# couch-int-rc.net
KiCad netlist of a schematic drawn in EAGLE
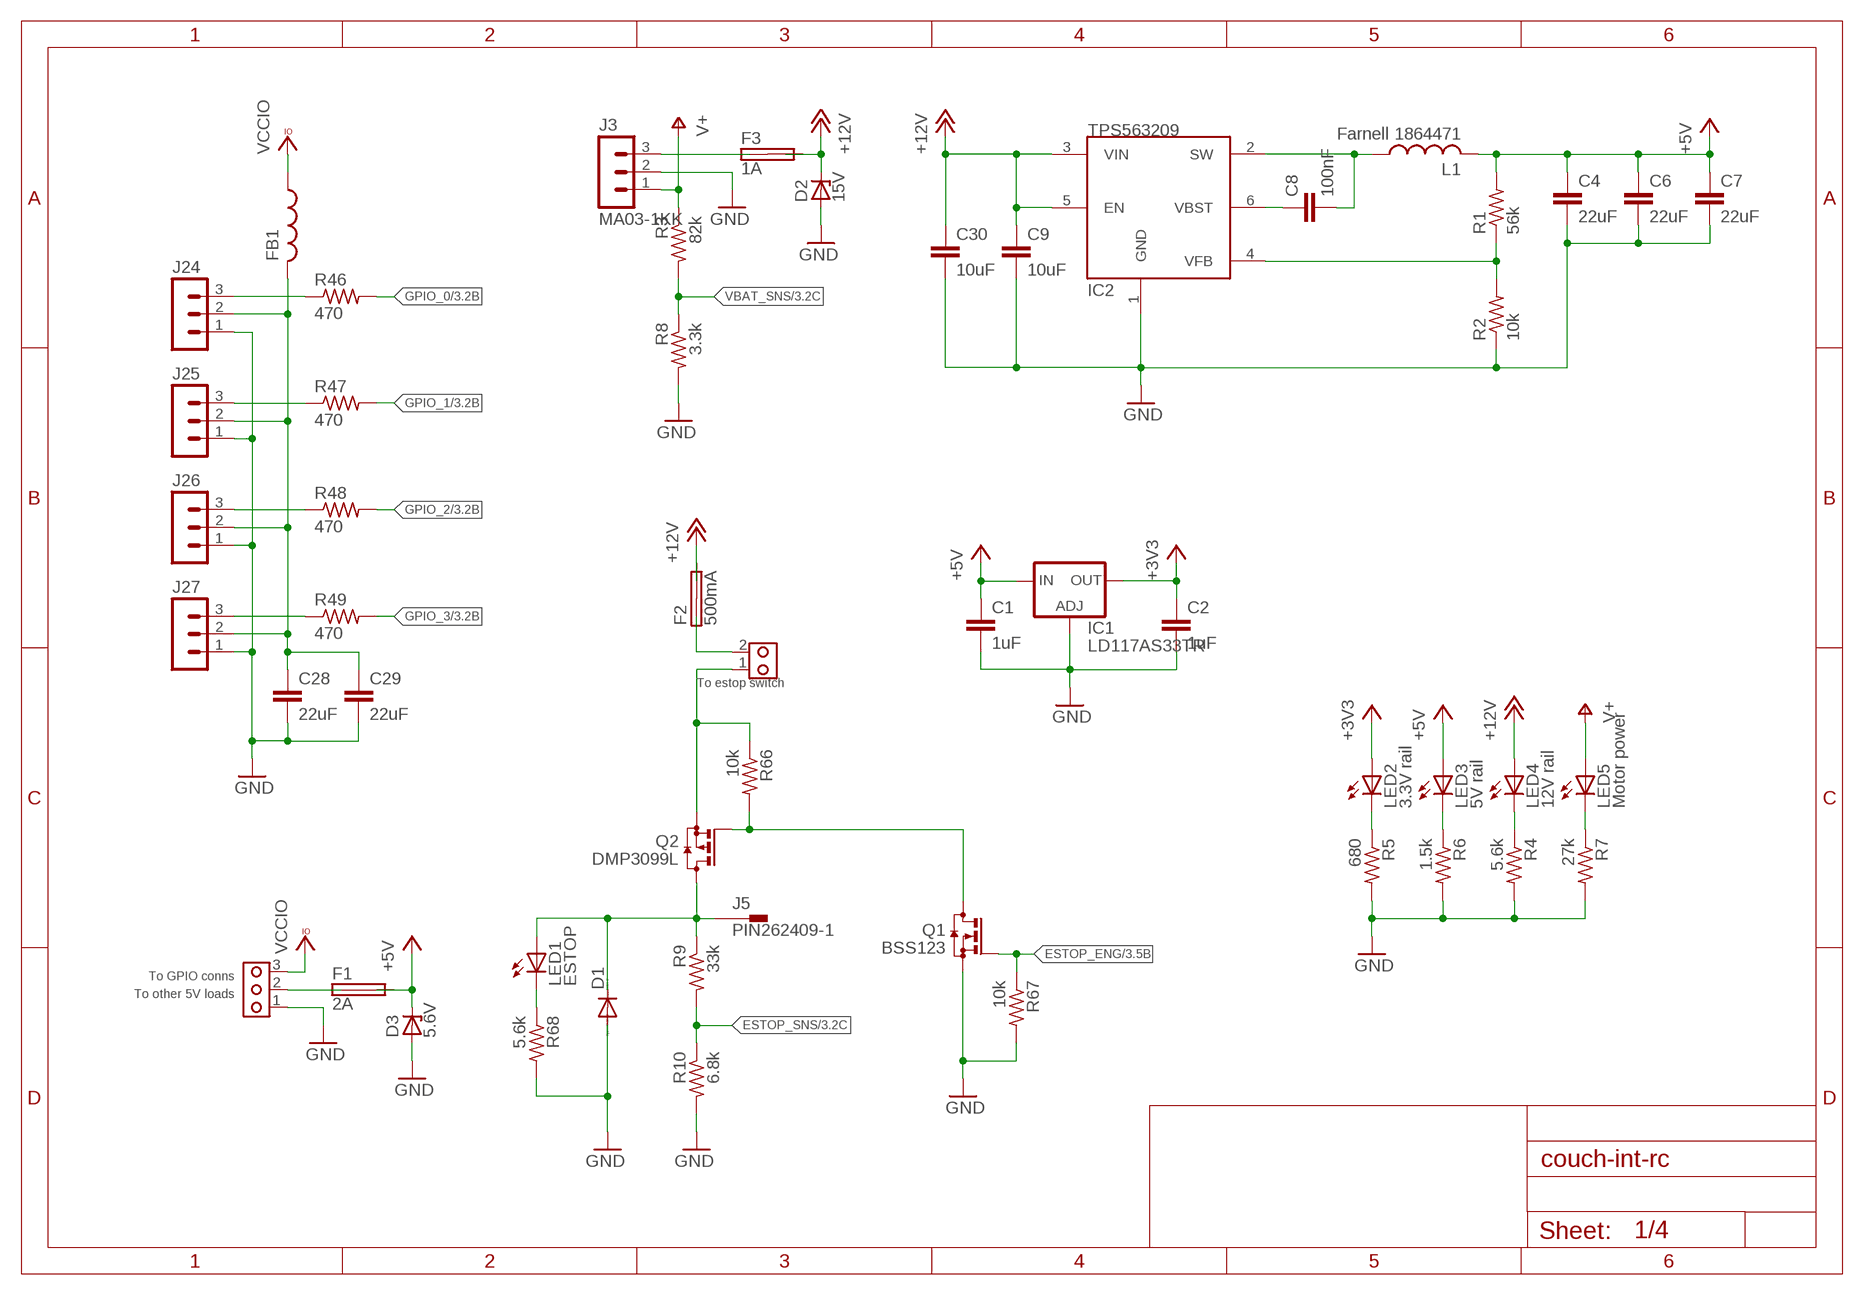
[diagram p0: schematic, sheet 1]
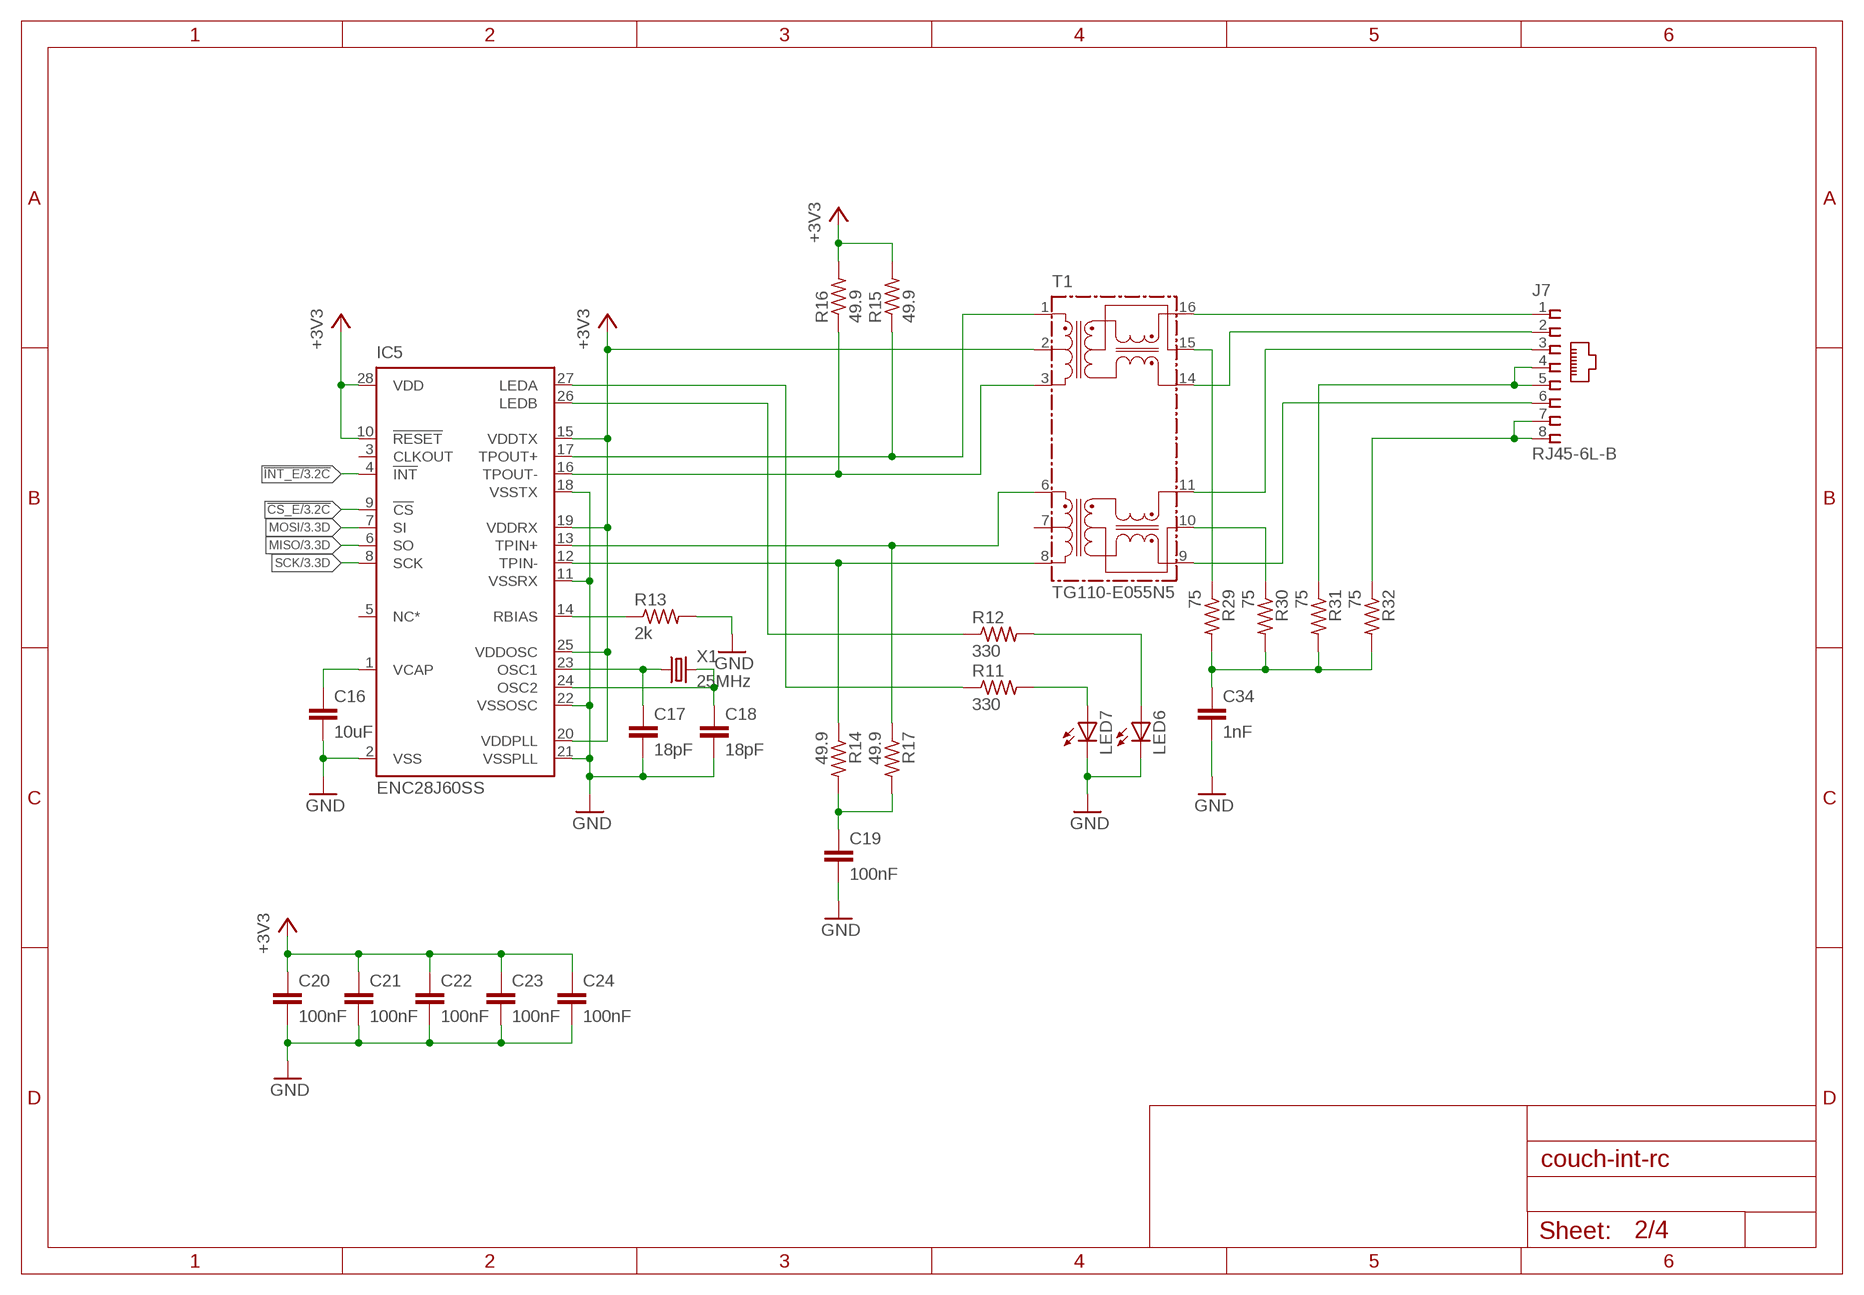
[diagram p1: schematic, sheet 2]
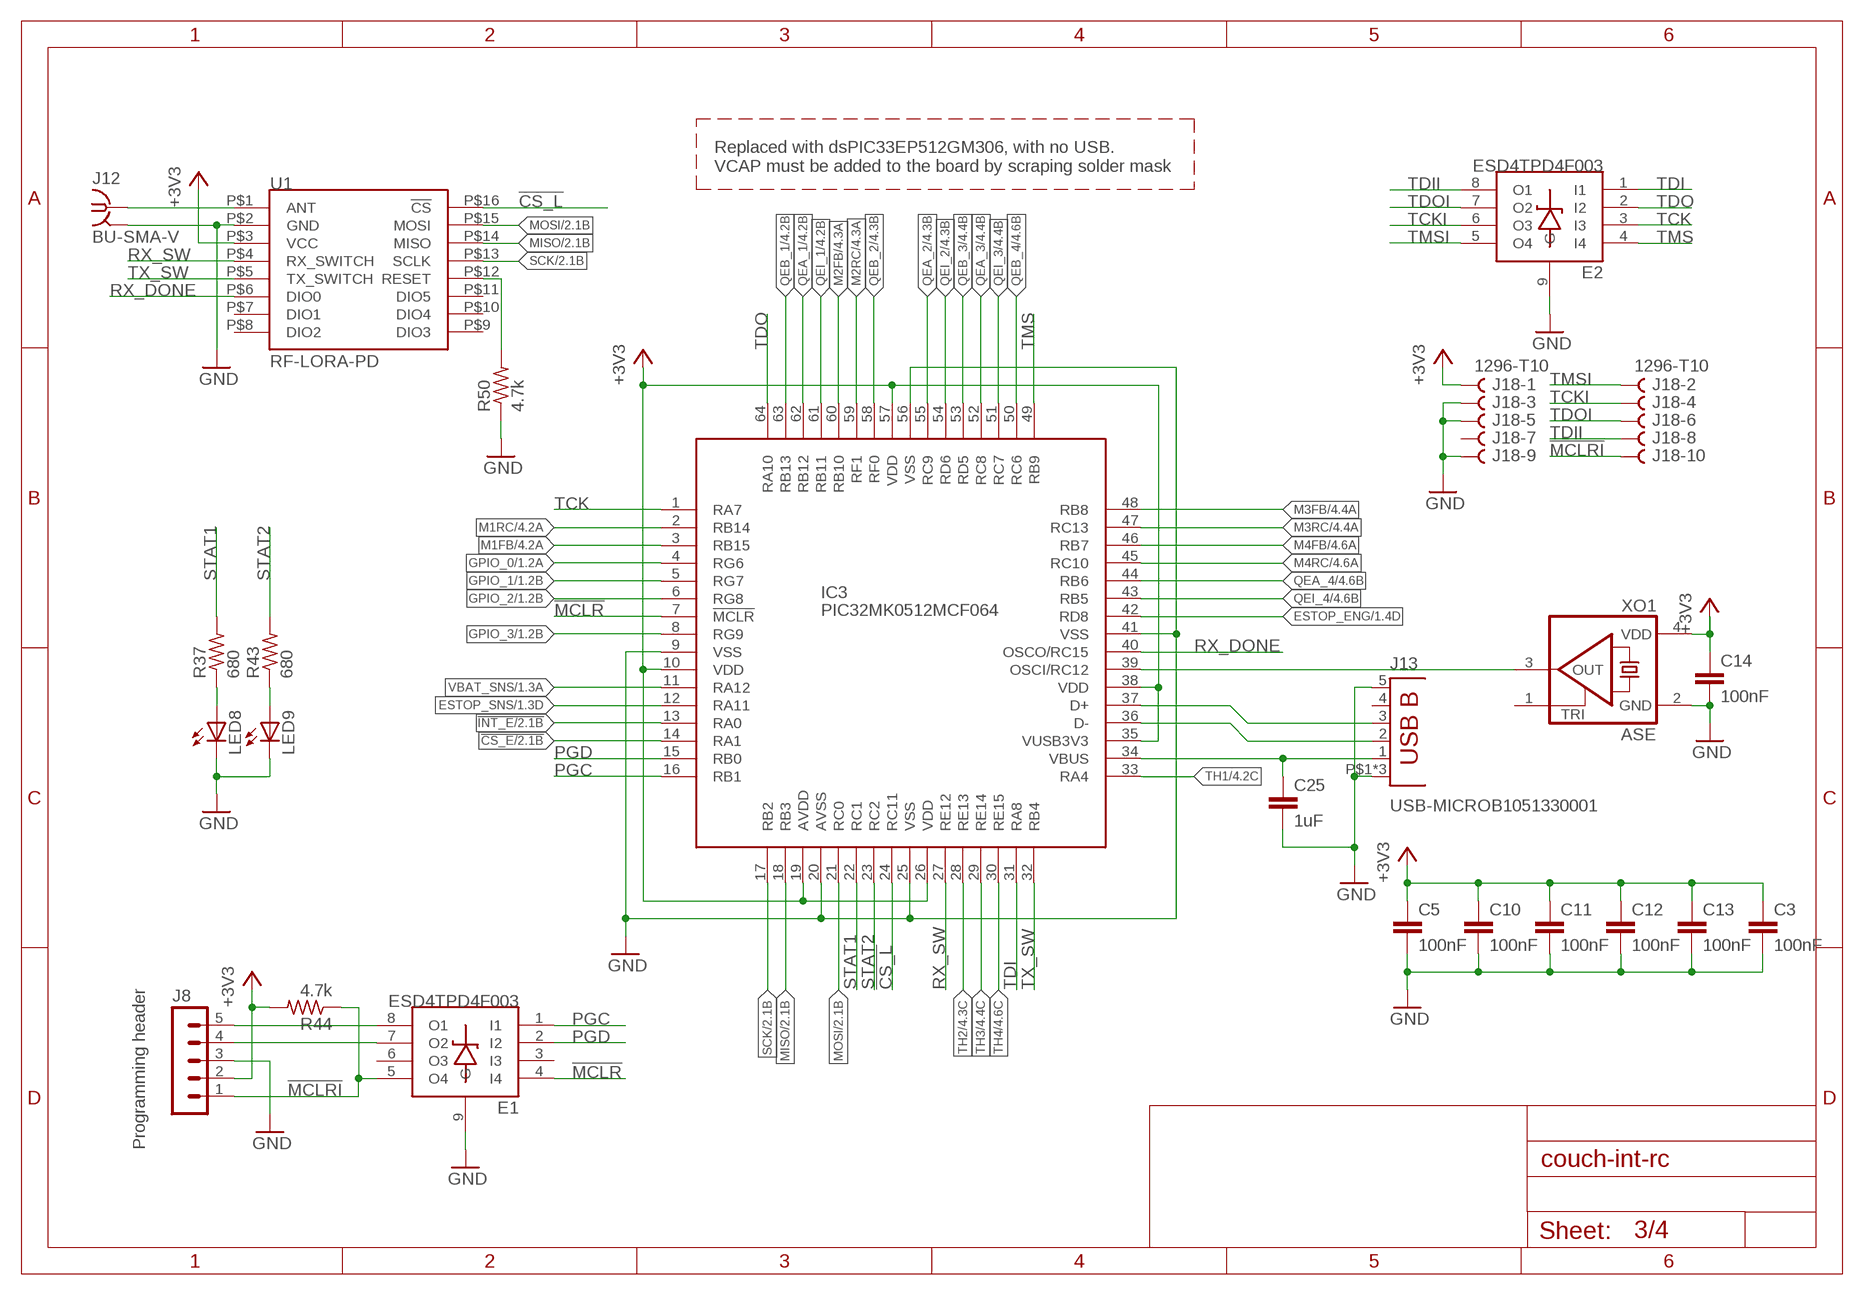
[diagram p2: schematic, sheet 3]
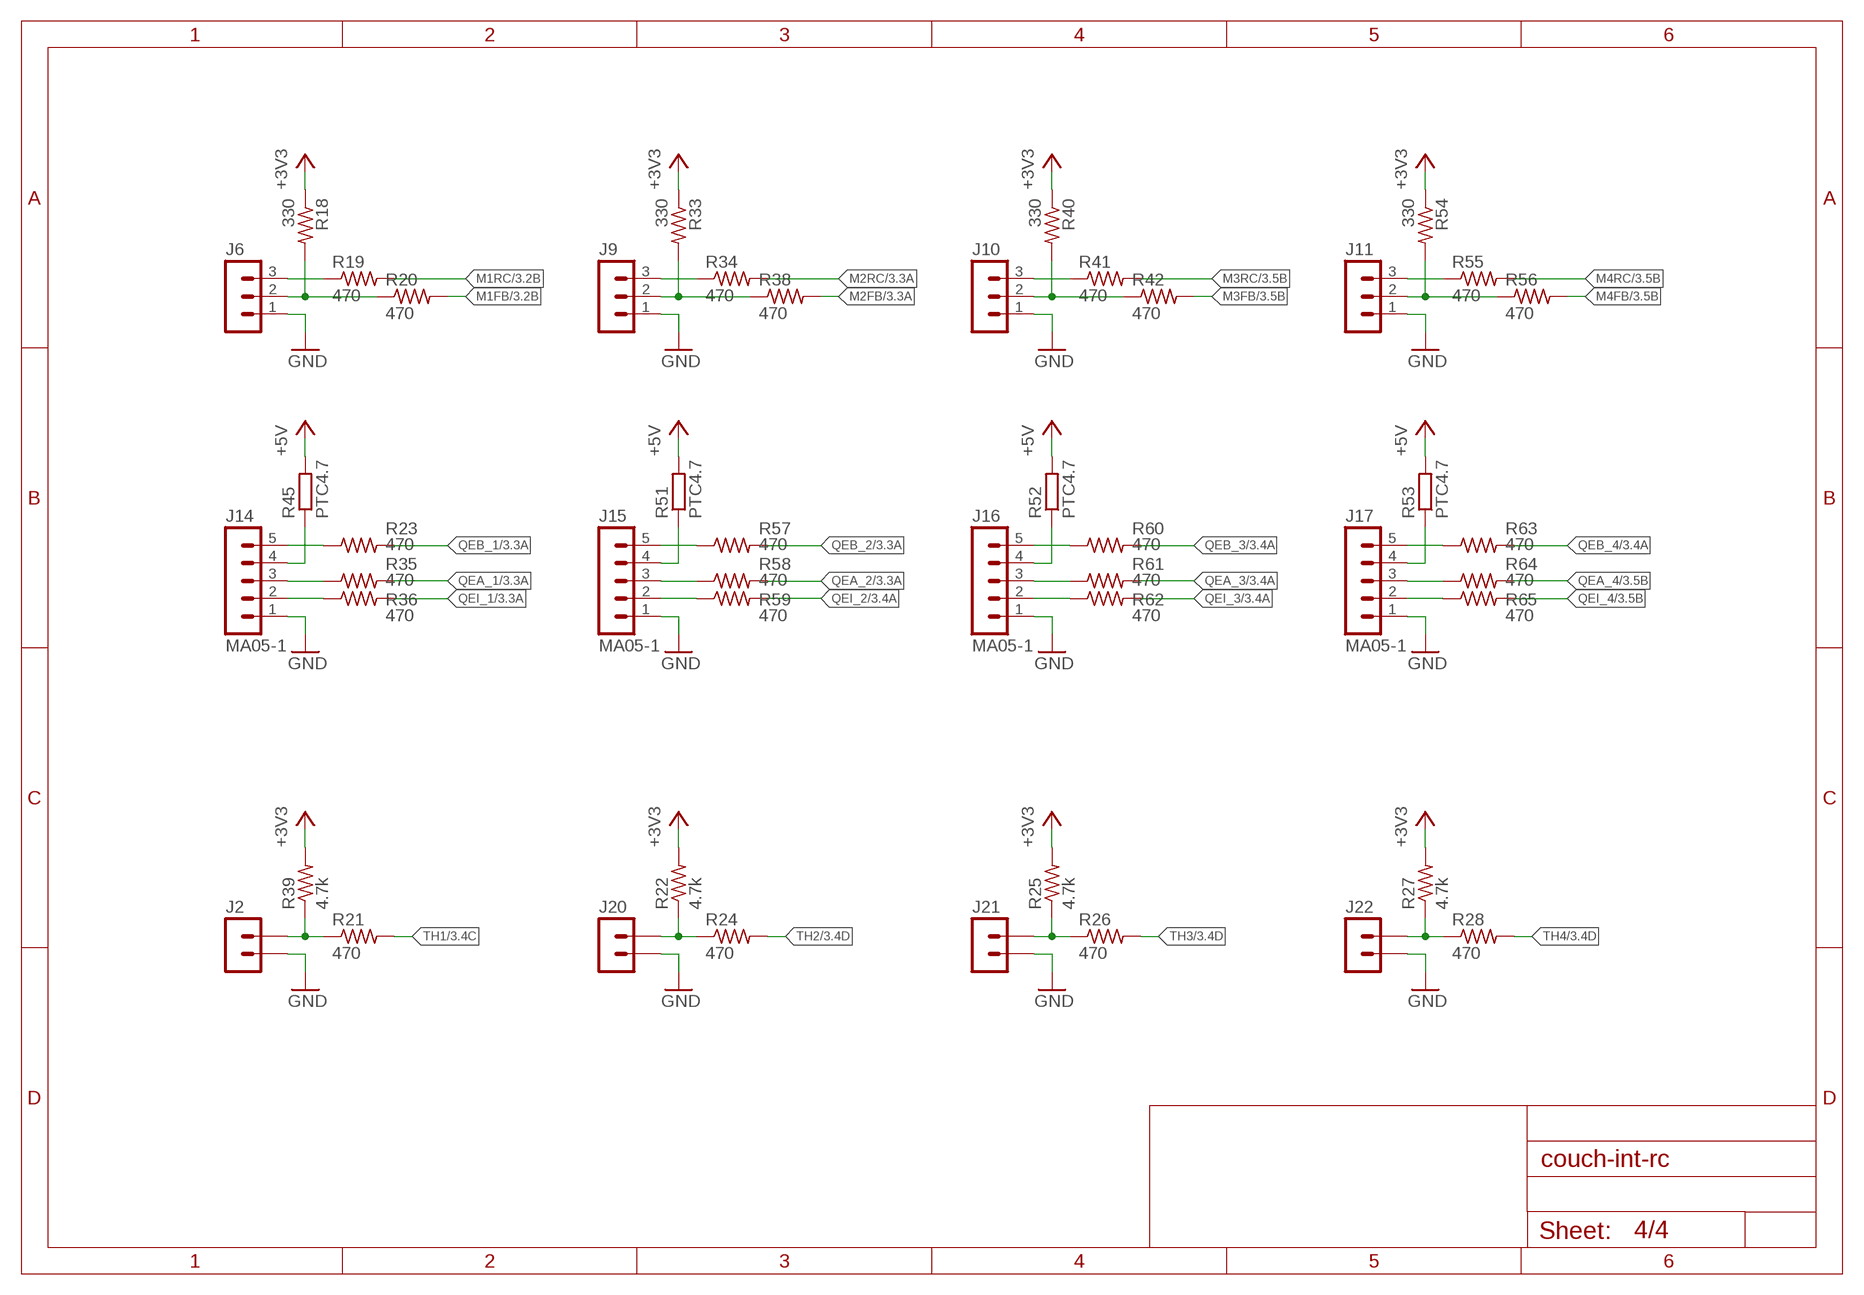
[diagram p3: schematic, sheet 4]

(export (version "E")
  (design (tool "Eeschema 10.0.6"))
  (components
    (comp (ref "J2")
      (value "MA02-1")
      (footprint "eagle-import:MOLEX-2")
      (libsource (lib "eagle-import") (part "MA02-1"))
    )
    (comp (ref "J6")
      (value "MA03-1")
      (footprint "eagle-import:MA03-1")
      (libsource (lib "eagle-import") (part "MA03-1"))
    )
    (comp (ref "J9")
      (value "MA03-1")
      (footprint "eagle-import:MA03-1")
      (libsource (lib "eagle-import") (part "MA03-1"))
    )
    (comp (ref "J10")
      (value "MA03-1")
      (footprint "eagle-import:MA03-1")
      (libsource (lib "eagle-import") (part "MA03-1"))
    )
    (comp (ref "J11")
      (value "MA03-1")
      (footprint "eagle-import:MA03-1")
      (libsource (lib "eagle-import") (part "MA03-1"))
    )
    (comp (ref "J14")
      (value "MA05-1")
      (footprint "eagle-import:MOLEX-5")
      (libsource (lib "eagle-import") (part "william_MA05-1"))
    )
    (comp (ref "J15")
      (value "MA05-1")
      (footprint "eagle-import:MOLEX-5")
      (libsource (lib "eagle-import") (part "william_MA05-1"))
    )
    (comp (ref "J16")
      (value "MA05-1")
      (footprint "eagle-import:MOLEX-5")
      (libsource (lib "eagle-import") (part "william_MA05-1"))
    )
    (comp (ref "J17")
      (value "MA05-1")
      (footprint "eagle-import:MOLEX-5")
      (libsource (lib "eagle-import") (part "william_MA05-1"))
    )
    (comp (ref "J20")
      (value "MA02-1")
      (footprint "eagle-import:MOLEX-2")
      (libsource (lib "eagle-import") (part "MA02-1"))
    )
    (comp (ref "J21")
      (value "MA02-1")
      (footprint "eagle-import:MOLEX-2")
      (libsource (lib "eagle-import") (part "MA02-1"))
    )
    (comp (ref "J22")
      (value "MA02-1")
      (footprint "eagle-import:MOLEX-2")
      (libsource (lib "eagle-import") (part "MA02-1"))
    )
    (comp (ref "R18")
      (value "330")
      (footprint "eagle-import:R0603")
      (libsource (lib "eagle-import") (part "R-US_R0603"))
    )
    (comp (ref "R19")
      (value "470")
      (footprint "eagle-import:R0603")
      (libsource (lib "eagle-import") (part "R-US_R0603"))
    )
    (comp (ref "R20")
      (value "470")
      (footprint "eagle-import:R0603")
      (libsource (lib "eagle-import") (part "R-US_R0603"))
    )
    (comp (ref "R21")
      (value "470")
      (footprint "eagle-import:R0603")
      (libsource (lib "eagle-import") (part "R-US_R0603"))
    )
    (comp (ref "R22")
      (value "4.7k")
      (footprint "eagle-import:R0603")
      (libsource (lib "eagle-import") (part "R-US_R0603"))
    )
    (comp (ref "R23")
      (value "470")
      (footprint "eagle-import:R0603")
      (libsource (lib "eagle-import") (part "R-US_R0603"))
    )
    (comp (ref "R24")
      (value "470")
      (footprint "eagle-import:R0603")
      (libsource (lib "eagle-import") (part "R-US_R0603"))
    )
    (comp (ref "R25")
      (value "4.7k")
      (footprint "eagle-import:R0603")
      (libsource (lib "eagle-import") (part "R-US_R0603"))
    )
    (comp (ref "R26")
      (value "470")
      (footprint "eagle-import:R0603")
      (libsource (lib "eagle-import") (part "R-US_R0603"))
    )
    (comp (ref "R27")
      (value "4.7k")
      (footprint "eagle-import:R0603")
      (libsource (lib "eagle-import") (part "R-US_R0603"))
    )
    (comp (ref "R28")
      (value "470")
      (footprint "eagle-import:R0603")
      (libsource (lib "eagle-import") (part "R-US_R0603"))
    )
    (comp (ref "R33")
      (value "330")
      (footprint "eagle-import:R0603")
      (libsource (lib "eagle-import") (part "R-US_R0603"))
    )
    (comp (ref "R34")
      (value "470")
      (footprint "eagle-import:R0603")
      (libsource (lib "eagle-import") (part "R-US_R0603"))
    )
    (comp (ref "R35")
      (value "470")
      (footprint "eagle-import:R0603")
      (libsource (lib "eagle-import") (part "R-US_R0603"))
    )
    (comp (ref "R36")
      (value "470")
      (footprint "eagle-import:R0603")
      (libsource (lib "eagle-import") (part "R-US_R0603"))
    )
    (comp (ref "R38")
      (value "470")
      (footprint "eagle-import:R0603")
      (libsource (lib "eagle-import") (part "R-US_R0603"))
    )
    (comp (ref "R39")
      (value "4.7k")
      (footprint "eagle-import:R0603")
      (libsource (lib "eagle-import") (part "R-US_R0603"))
    )
    (comp (ref "R40")
      (value "330")
      (footprint "eagle-import:R0603")
      (libsource (lib "eagle-import") (part "R-US_R0603"))
    )
    (comp (ref "R41")
      (value "470")
      (footprint "eagle-import:R0603")
      (libsource (lib "eagle-import") (part "R-US_R0603"))
    )
    (comp (ref "R42")
      (value "470")
      (footprint "eagle-import:R0603")
      (libsource (lib "eagle-import") (part "R-US_R0603"))
    )
    (comp (ref "R45")
      (value "PTC4.7")
      (footprint "eagle-import:R0603")
      (libsource (lib "eagle-import") (part "R-EU_R0603"))
    )
    (comp (ref "R51")
      (value "PTC4.7")
      (footprint "eagle-import:R0603")
      (libsource (lib "eagle-import") (part "R-EU_R0603"))
    )
    (comp (ref "R52")
      (value "PTC4.7")
      (footprint "eagle-import:R0603")
      (libsource (lib "eagle-import") (part "R-EU_R0603"))
    )
    (comp (ref "R53")
      (value "PTC4.7")
      (footprint "eagle-import:R0603")
      (libsource (lib "eagle-import") (part "R-EU_R0603"))
    )
    (comp (ref "R54")
      (value "330")
      (footprint "eagle-import:R0603")
      (libsource (lib "eagle-import") (part "R-US_R0603"))
    )
    (comp (ref "R55")
      (value "470")
      (footprint "eagle-import:R0603")
      (libsource (lib "eagle-import") (part "R-US_R0603"))
    )
    (comp (ref "R56")
      (value "470")
      (footprint "eagle-import:R0603")
      (libsource (lib "eagle-import") (part "R-US_R0603"))
    )
    (comp (ref "R57")
      (value "470")
      (footprint "eagle-import:R0603")
      (libsource (lib "eagle-import") (part "R-US_R0603"))
    )
    (comp (ref "R58")
      (value "470")
      (footprint "eagle-import:R0603")
      (libsource (lib "eagle-import") (part "R-US_R0603"))
    )
    (comp (ref "R59")
      (value "470")
      (footprint "eagle-import:R0603")
      (libsource (lib "eagle-import") (part "R-US_R0603"))
    )
    (comp (ref "R60")
      (value "470")
      (footprint "eagle-import:R0603")
      (libsource (lib "eagle-import") (part "R-US_R0603"))
    )
    (comp (ref "R61")
      (value "470")
      (footprint "eagle-import:R0603")
      (libsource (lib "eagle-import") (part "R-US_R0603"))
    )
    (comp (ref "R62")
      (value "470")
      (footprint "eagle-import:R0603")
      (libsource (lib "eagle-import") (part "R-US_R0603"))
    )
    (comp (ref "R63")
      (value "470")
      (footprint "eagle-import:R0603")
      (libsource (lib "eagle-import") (part "R-US_R0603"))
    )
    (comp (ref "R64")
      (value "470")
      (footprint "eagle-import:R0603")
      (libsource (lib "eagle-import") (part "R-US_R0603"))
    )
    (comp (ref "R65")
      (value "470")
      (footprint "eagle-import:R0603")
      (libsource (lib "eagle-import") (part "R-US_R0603"))
    )
    (comp (ref "C16")
      (value "10uF")
      (footprint "eagle-import:C0603")
      (libsource (lib "eagle-import") (part "C-EUC0603"))
    )
    (comp (ref "C17")
      (value "18pF")
      (footprint "eagle-import:C0603")
      (libsource (lib "eagle-import") (part "C-EUC0603"))
    )
    (comp (ref "C18")
      (value "18pF")
      (footprint "eagle-import:C0603")
      (libsource (lib "eagle-import") (part "C-EUC0603"))
    )
    (comp (ref "C19")
      (value "100nF")
      (footprint "eagle-import:C0603")
      (libsource (lib "eagle-import") (part "C-EUC0603"))
    )
    (comp (ref "C20")
      (value "100nF")
      (footprint "eagle-import:C0603")
      (libsource (lib "eagle-import") (part "C-EUC0603"))
    )
    (comp (ref "C21")
      (value "100nF")
      (footprint "eagle-import:C0603")
      (libsource (lib "eagle-import") (part "C-EUC0603"))
    )
    (comp (ref "C22")
      (value "100nF")
      (footprint "eagle-import:C0603")
      (libsource (lib "eagle-import") (part "C-EUC0603"))
    )
    (comp (ref "C23")
      (value "100nF")
      (footprint "eagle-import:C0603")
      (libsource (lib "eagle-import") (part "C-EUC0603"))
    )
    (comp (ref "C24")
      (value "100nF")
      (footprint "eagle-import:C0603")
      (libsource (lib "eagle-import") (part "C-EUC0603"))
    )
    (comp (ref "C34")
      (value "1nF")
      (footprint "eagle-import:C0603")
      (libsource (lib "eagle-import") (part "C-EUC0603"))
    )
    (comp (ref "IC5")
      (value "ENC28J60SS")
      (footprint "eagle-import:SSOP-28")
      (libsource (lib "eagle-import") (part "ENC28J60SS"))
    )
    (comp (ref "J7")
      (value "RJ45-6L-B")
      (footprint "eagle-import:RJ45-NO-SHIELD")
      (libsource (lib "eagle-import") (part "RJ45-6L-B"))
    )
    (comp (ref "LED6")
      (value "LEDCHIP-LED0603")
      (footprint "eagle-import:CHIP-LED0603")
      (libsource (lib "eagle-import") (part "LEDCHIP-LED0603"))
    )
    (comp (ref "LED7")
      (value "LEDCHIP-LED0603")
      (footprint "eagle-import:CHIP-LED0603")
      (libsource (lib "eagle-import") (part "LEDCHIP-LED0603"))
    )
    (comp (ref "R11")
      (value "330")
      (footprint "eagle-import:R0603")
      (libsource (lib "eagle-import") (part "R-US_R0603"))
    )
    (comp (ref "R12")
      (value "330")
      (footprint "eagle-import:R0603")
      (libsource (lib "eagle-import") (part "R-US_R0603"))
    )
    (comp (ref "R13")
      (value "2k")
      (footprint "eagle-import:R0603")
      (libsource (lib "eagle-import") (part "R-US_R0603"))
    )
    (comp (ref "R14")
      (value "49.9")
      (footprint "eagle-import:R0603")
      (libsource (lib "eagle-import") (part "R-US_R0603"))
    )
    (comp (ref "R15")
      (value "49.9")
      (footprint "eagle-import:R0603")
      (libsource (lib "eagle-import") (part "R-US_R0603"))
    )
    (comp (ref "R16")
      (value "49.9")
      (footprint "eagle-import:R0603")
      (libsource (lib "eagle-import") (part "R-US_R0603"))
    )
    (comp (ref "R17")
      (value "49.9")
      (footprint "eagle-import:R0603")
      (libsource (lib "eagle-import") (part "R-US_R0603"))
    )
    (comp (ref "R29")
      (value "75")
      (footprint "eagle-import:R0603")
      (libsource (lib "eagle-import") (part "R-US_R0603"))
    )
    (comp (ref "R30")
      (value "75")
      (footprint "eagle-import:R0603")
      (libsource (lib "eagle-import") (part "R-US_R0603"))
    )
    (comp (ref "R31")
      (value "75")
      (footprint "eagle-import:R0603")
      (libsource (lib "eagle-import") (part "R-US_R0603"))
    )
    (comp (ref "R32")
      (value "75")
      (footprint "eagle-import:R0603")
      (libsource (lib "eagle-import") (part "R-US_R0603"))
    )
    (comp (ref "T1")
      (value "TG110-E055N5")
      (footprint "eagle-import:N5")
      (libsource (lib "eagle-import") (part "TG110-EN5055"))
    )
    (comp (ref "X1")
      (value "25MHz")
      (footprint "eagle-import:HC49_S")
      (libsource (lib "eagle-import") (part "CRYSTALHC49S"))
    )
    (comp (ref "C1")
      (value "1uF")
      (footprint "eagle-import:C0603")
      (libsource (lib "eagle-import") (part "C-EUC0603"))
    )
    (comp (ref "C2")
      (value "1uF")
      (footprint "eagle-import:C0603")
      (libsource (lib "eagle-import") (part "C-EUC0603"))
    )
    (comp (ref "C4")
      (value "22uF")
      (footprint "eagle-import:C1206")
      (libsource (lib "eagle-import") (part "C-EUC1206"))
    )
    (comp (ref "C6")
      (value "22uF")
      (footprint "eagle-import:C1206")
      (libsource (lib "eagle-import") (part "C-EUC1206"))
    )
    (comp (ref "C7")
      (value "22uF")
      (footprint "eagle-import:C1206")
      (libsource (lib "eagle-import") (part "C-EUC1206"))
    )
    (comp (ref "C8")
      (value "100nF")
      (footprint "eagle-import:C0603")
      (libsource (lib "eagle-import") (part "C-EUC0603"))
    )
    (comp (ref "C9")
      (value "10uF")
      (footprint "eagle-import:C1206")
      (libsource (lib "eagle-import") (part "C-EUC1206"))
    )
    (comp (ref "C28")
      (value "22uF")
      (footprint "eagle-import:C1206")
      (libsource (lib "eagle-import") (part "C-EUC1206"))
    )
    (comp (ref "C29")
      (value "22uF")
      (footprint "eagle-import:C1206")
      (libsource (lib "eagle-import") (part "C-EUC1206"))
    )
    (comp (ref "C30")
      (value "10uF")
      (footprint "eagle-import:C1206")
      (libsource (lib "eagle-import") (part "C-EUC1206"))
    )
    (comp (ref "D1")
      (value "DIODE-SMB")
      (footprint "eagle-import:SMB")
      (libsource (lib "eagle-import") (part "DIODE-SMB"))
    )
    (comp (ref "D2")
      (value "15V")
      (footprint "eagle-import:SOD80C")
      (libsource (lib "eagle-import") (part "ZENER-DIODESOD80C"))
    )
    (comp (ref "D3")
      (value "5.6V")
      (footprint "eagle-import:SOD80C")
      (libsource (lib "eagle-import") (part "ZENER-DIODESOD80C"))
    )
    (comp (ref "F1")
      (value "2A")
      (footprint "eagle-import:SHK20L")
      (libsource (lib "eagle-import") (part "FUSESHK20L"))
    )
    (comp (ref "F2")
      (value "500mA")
      (footprint "eagle-import:SHK20L")
      (libsource (lib "eagle-import") (part "SHK20L"))
    )
    (comp (ref "F3")
      (value "1A")
      (footprint "eagle-import:SHK20L")
      (libsource (lib "eagle-import") (part "SHK20L"))
    )
    (comp (ref "FB1")
      (value "L-USL3216C")
      (footprint "eagle-import:L3216C")
      (libsource (lib "eagle-import") (part "L-USL3216C"))
    )
    (comp (ref "IC1")
      (value "LD117AS33TR")
      (footprint "eagle-import:SOT223")
      (libsource (lib "eagle-import") (part "LD117A?S33TR"))
    )
    (comp (ref "IC2")
      (value "TPS563209")
      (footprint "eagle-import:SOT23-6")
      (libsource (lib "eagle-import") (part "TPS562093"))
    )
    (comp (ref "J1")
      (value "PCBTERM3")
      (footprint "eagle-import:PCBTERM3")
      (libsource (lib "eagle-import") (part "PCBTERM3"))
    )
    (comp (ref "J3")
      (value "MA03-1KK")
      (footprint "eagle-import:MOLEX-3")
      (libsource (lib "eagle-import") (part "MA03-1KK"))
    )
    (comp (ref "J4")
      (value "PCBTERM2")
      (footprint "eagle-import:PCBTERM")
      (libsource (lib "eagle-import") (part "PCBTERM2"))
    )
    (comp (ref "J5")
      (value "PIN262409-1")
      (footprint "eagle-import:62409-1")
      (libsource (lib "eagle-import") (part "PIN262409-1"))
    )
    (comp (ref "J24")
      (value "MA03-1")
      (footprint "eagle-import:MA03-1")
      (libsource (lib "eagle-import") (part "MA03-1"))
    )
    (comp (ref "J25")
      (value "MA03-1")
      (footprint "eagle-import:MA03-1")
      (libsource (lib "eagle-import") (part "MA03-1"))
    )
    (comp (ref "J26")
      (value "MA03-1")
      (footprint "eagle-import:MA03-1")
      (libsource (lib "eagle-import") (part "MA03-1"))
    )
    (comp (ref "J27")
      (value "MA03-1")
      (footprint "eagle-import:MA03-1")
      (libsource (lib "eagle-import") (part "MA03-1"))
    )
    (comp (ref "L1")
      (value "Farnell 1864471")
      (footprint "eagle-import:MCSDRH73B")
      (libsource (lib "eagle-import") (part "L_USMCSDRH73B"))
    )
    (comp (ref "LED1")
      (value "ESTOP")
      (footprint "eagle-import:CHIPLED_0603")
      (libsource (lib "eagle-import") (part "LEDCHIPLED_0603"))
    )
    (comp (ref "LED2")
      (value "3.3V rail")
      (footprint "eagle-import:CHIPLED_0603")
      (libsource (lib "eagle-import") (part "LEDCHIPLED_0603"))
    )
    (comp (ref "LED3")
      (value "5V rail")
      (footprint "eagle-import:CHIPLED_0603")
      (libsource (lib "eagle-import") (part "LEDCHIPLED_0603"))
    )
    (comp (ref "LED4")
      (value "12V rail")
      (footprint "eagle-import:CHIPLED_0603")
      (libsource (lib "eagle-import") (part "LEDCHIPLED_0603"))
    )
    (comp (ref "LED5")
      (value "Motor power")
      (footprint "eagle-import:CHIPLED_0603")
      (libsource (lib "eagle-import") (part "LEDCHIPLED_0603"))
    )
    (comp (ref "Q1")
      (value "BSS123")
      (footprint "eagle-import:SOT23")
      (libsource (lib "eagle-import") (part "BSS123"))
    )
    (comp (ref "Q2")
      (value "DMP3099L")
      (footprint "eagle-import:SOT23")
      (libsource (lib "eagle-import") (part "BSS84"))
    )
    (comp (ref "R1")
      (value "56k")
      (footprint "eagle-import:R0603")
      (libsource (lib "eagle-import") (part "R-US_R0603"))
    )
    (comp (ref "R2")
      (value "10k")
      (footprint "eagle-import:R0603")
      (libsource (lib "eagle-import") (part "R-US_R0603"))
    )
    (comp (ref "R3")
      (value "82k")
      (footprint "eagle-import:R0603")
      (libsource (lib "eagle-import") (part "R-US_R0603"))
    )
    (comp (ref "R4")
      (value "5.6k")
      (footprint "eagle-import:R0603")
      (libsource (lib "eagle-import") (part "R-US_R0603"))
    )
    (comp (ref "R5")
      (value "680")
      (footprint "eagle-import:R0603")
      (libsource (lib "eagle-import") (part "R-US_R0603"))
    )
    (comp (ref "R6")
      (value "1.5k")
      (footprint "eagle-import:R0603")
      (libsource (lib "eagle-import") (part "R-US_R0603"))
    )
    (comp (ref "R7")
      (value "27k")
      (footprint "eagle-import:R0603")
      (libsource (lib "eagle-import") (part "R-US_R0603"))
    )
    (comp (ref "R8")
      (value "3.3k")
      (footprint "eagle-import:R0603")
      (libsource (lib "eagle-import") (part "R-US_R0603"))
    )
    (comp (ref "R9")
      (value "33k")
      (footprint "eagle-import:R0603")
      (libsource (lib "eagle-import") (part "R-US_R0603"))
    )
    (comp (ref "R10")
      (value "6.8k")
      (footprint "eagle-import:R0603")
      (libsource (lib "eagle-import") (part "R-US_R0603"))
    )
    (comp (ref "R46")
      (value "470")
      (footprint "eagle-import:R0603")
      (libsource (lib "eagle-import") (part "R-US_R0603"))
    )
    (comp (ref "R47")
      (value "470")
      (footprint "eagle-import:R0603")
      (libsource (lib "eagle-import") (part "R-US_R0603"))
    )
    (comp (ref "R48")
      (value "470")
      (footprint "eagle-import:R0603")
      (libsource (lib "eagle-import") (part "R-US_R0603"))
    )
    (comp (ref "R49")
      (value "470")
      (footprint "eagle-import:R0603")
      (libsource (lib "eagle-import") (part "R-US_R0603"))
    )
    (comp (ref "R66")
      (value "10k")
      (footprint "eagle-import:R0603")
      (libsource (lib "eagle-import") (part "R-US_R0603"))
    )
    (comp (ref "R67")
      (value "10k")
      (footprint "eagle-import:R0603")
      (libsource (lib "eagle-import") (part "R-US_R0603"))
    )
    (comp (ref "R68")
      (value "5.6k")
      (footprint "eagle-import:R0603")
      (libsource (lib "eagle-import") (part "R-US_R0603"))
    )
    (comp (ref "C3")
      (value "100nF")
      (footprint "eagle-import:C0603")
      (libsource (lib "eagle-import") (part "C-EUC0603"))
    )
    (comp (ref "C5")
      (value "100nF")
      (footprint "eagle-import:C0603")
      (libsource (lib "eagle-import") (part "C-EUC0603"))
    )
    (comp (ref "C10")
      (value "100nF")
      (footprint "eagle-import:C0603")
      (libsource (lib "eagle-import") (part "C-EUC0603"))
    )
    (comp (ref "C11")
      (value "100nF")
      (footprint "eagle-import:C0603")
      (libsource (lib "eagle-import") (part "C-EUC0603"))
    )
    (comp (ref "C12")
      (value "100nF")
      (footprint "eagle-import:C0603")
      (libsource (lib "eagle-import") (part "C-EUC0603"))
    )
    (comp (ref "C13")
      (value "100nF")
      (footprint "eagle-import:C0603")
      (libsource (lib "eagle-import") (part "C-EUC0603"))
    )
    (comp (ref "C14")
      (value "100nF")
      (footprint "eagle-import:C0603")
      (libsource (lib "eagle-import") (part "C-EUC0603"))
    )
    (comp (ref "C25")
      (value "1uF")
      (footprint "eagle-import:C0603")
      (libsource (lib "eagle-import") (part "C-EUC0603"))
    )
    (comp (ref "E1")
      (value "ESD4TPD4F003")
      (footprint "eagle-import:WSON-8")
      (libsource (lib "eagle-import") (part "ESD4TPD4F003"))
    )
    (comp (ref "E2")
      (value "ESD4TPD4F003")
      (footprint "eagle-import:WSON-8")
      (libsource (lib "eagle-import") (part "ESD4TPD4F003"))
    )
    (comp (ref "IC3")
      (value "PIC32MK0512MCF064")
      (footprint "eagle-import:TQFP-64-10")
      (libsource (lib "eagle-import") (part "PIC32MKMCF0640512"))
    )
    (comp (ref "J8")
      (value "MA05-1")
      (footprint "eagle-import:MA05-1")
      (libsource (lib "eagle-import") (part "MA05-1"))
    )
    (comp (ref "J12")
      (value "BU-SMA-V")
      (footprint "eagle-import:BU-SMA-V")
      (libsource (lib "eagle-import") (part "BU-SMA-V"))
    )
    (comp (ref "J13")
      (value "USB-MICROB1051330001")
      (footprint "eagle-import:1051330001")
      (libsource (lib "eagle-import") (part "USB-MICROB1051330001"))
    )
    (comp (ref "J18")
      (value "1296-T10")
      (footprint "eagle-import:1296-10")
      (libsource (lib "eagle-import") (part "1296-T10"))
    )
    (comp (ref "LED8")
      (value "LEDCHIP-LED0603")
      (footprint "eagle-import:CHIP-LED0603")
      (libsource (lib "eagle-import") (part "LEDCHIP-LED0603"))
    )
    (comp (ref "LED9")
      (value "LEDCHIP-LED0603")
      (footprint "eagle-import:CHIP-LED0603")
      (libsource (lib "eagle-import") (part "LEDCHIP-LED0603"))
    )
    (comp (ref "R37")
      (value "680")
      (footprint "eagle-import:R0603")
      (libsource (lib "eagle-import") (part "R-US_R0603"))
    )
    (comp (ref "R43")
      (value "680")
      (footprint "eagle-import:R0603")
      (libsource (lib "eagle-import") (part "R-US_R0603"))
    )
    (comp (ref "R44")
      (value "4.7k")
      (footprint "eagle-import:R0603")
      (libsource (lib "eagle-import") (part "R-US_R0603"))
    )
    (comp (ref "R50")
      (value "4.7k")
      (footprint "eagle-import:R0603")
      (libsource (lib "eagle-import") (part "R-US_R0603"))
    )
    (comp (ref "U1")
      (value "RF-LORA-PD")
      (footprint "eagle-import:RF-LORA-DIP")
      (libsource (lib "eagle-import") (part "RF-LORA-PD"))
    )
    (comp (ref "XO1")
      (value "ASE")
      (footprint "eagle-import:ASE")
      (libsource (lib "eagle-import") (part "ASE"))
    )
  )
  (nets
    (net (code "1") (name "+3V3") (class "Default")
      (node (ref "C10") (pin "1") (pinfunction "1_1") (pintype "passive"))
      (node (ref "C11") (pin "1") (pinfunction "1_1") (pintype "passive"))
      (node (ref "C12") (pin "1") (pinfunction "1_1") (pintype "passive"))
      (node (ref "C13") (pin "1") (pinfunction "1_1") (pintype "passive"))
      (node (ref "C14") (pin "1") (pinfunction "1_1") (pintype "passive"))
      (node (ref "C2") (pin "1") (pinfunction "1_1") (pintype "passive"))
      (node (ref "C20") (pin "1") (pinfunction "1_1") (pintype "passive"))
      (node (ref "C21") (pin "1") (pinfunction "1_1") (pintype "passive"))
      (node (ref "C22") (pin "1") (pinfunction "1_1") (pintype "passive"))
      (node (ref "C23") (pin "1") (pinfunction "1_1") (pintype "passive"))
      (node (ref "C24") (pin "1") (pinfunction "1_1") (pintype "passive"))
      (node (ref "C3") (pin "1") (pinfunction "1_1") (pintype "passive"))
      (node (ref "C5") (pin "1") (pinfunction "1_1") (pintype "passive"))
      (node (ref "IC1") (pin "4") (pinfunction "OUT_4") (pintype "passive"))
      (node (ref "IC3") (pin "10") (pinfunction "VDD_10") (pintype "power_in"))
      (node (ref "IC3") (pin "19") (pinfunction "AVDD_19") (pintype "power_in"))
      (node (ref "IC3") (pin "26") (pinfunction "VDD_26") (pintype "power_in"))
      (node (ref "IC3") (pin "35") (pinfunction "VUSB3V3_35") (pintype "bidirectional"))
      (node (ref "IC3") (pin "38") (pinfunction "VDD_38") (pintype "power_in"))
      (node (ref "IC3") (pin "57") (pinfunction "VDD_57") (pintype "power_in"))
      (node (ref "IC5") (pin "10") (pinfunction "~{RESET}_10") (pintype "input"))
      (node (ref "IC5") (pin "15") (pinfunction "VDDTX_15") (pintype "input"))
      (node (ref "IC5") (pin "19") (pinfunction "VDDRX_19") (pintype "input"))
      (node (ref "IC5") (pin "20") (pinfunction "VDDPLL_20") (pintype "input"))
      (node (ref "IC5") (pin "25") (pinfunction "VDDOSC_25") (pintype "input"))
      (node (ref "IC5") (pin "28") (pinfunction "VDD_28") (pintype "input"))
      (node (ref "J18") (pin "1") (pinfunction "B_1") (pintype "passive"))
      (node (ref "J8") (pin "2") (pinfunction "2_2") (pintype "passive"))
      (node (ref "LED2") (pin "A") (pinfunction "A_A") (pintype "passive"))
      (node (ref "R15") (pin "2") (pinfunction "2_2") (pintype "passive"))
      (node (ref "R16") (pin "2") (pinfunction "2_2") (pintype "passive"))
      (node (ref "R18") (pin "1") (pinfunction "1_1") (pintype "passive"))
      (node (ref "R22") (pin "2") (pinfunction "2_2") (pintype "passive"))
      (node (ref "R25") (pin "2") (pinfunction "2_2") (pintype "passive"))
      (node (ref "R27") (pin "2") (pinfunction "2_2") (pintype "passive"))
      (node (ref "R33") (pin "1") (pinfunction "1_1") (pintype "passive"))
      (node (ref "R39") (pin "2") (pinfunction "2_2") (pintype "passive"))
      (node (ref "R40") (pin "1") (pinfunction "1_1") (pintype "passive"))
      (node (ref "R44") (pin "2") (pinfunction "2_2") (pintype "passive"))
      (node (ref "R54") (pin "1") (pinfunction "1_1") (pintype "passive"))
      (node (ref "T1") (pin "2") (pinfunction "2_2") (pintype "passive"))
      (node (ref "U1") (pin "P$3") (pinfunction "VCC_P$3") (pintype "power_in"))
      (node (ref "XO1") (pin "4") (pinfunction "VDD_4") (pintype "power_in"))
    )
    (net (code "2") (name "+5V") (class "Default")
      (node (ref "C1") (pin "1") (pinfunction "1_1") (pintype "passive"))
      (node (ref "C4") (pin "1") (pinfunction "1_1") (pintype "passive"))
      (node (ref "C6") (pin "1") (pinfunction "1_1") (pintype "passive"))
      (node (ref "C7") (pin "1") (pinfunction "1_1") (pintype "passive"))
      (node (ref "D3") (pin "C") (pinfunction "C_C") (pintype "passive"))
      (node (ref "F1") (pin "2A") (pinfunction "2_2A") (pintype "passive"))
      (node (ref "F1") (pin "2B") (pinfunction "2_2B") (pintype "passive"))
      (node (ref "IC1") (pin "3") (pinfunction "IN_3") (pintype "input"))
      (node (ref "L1") (pin "P$2") (pinfunction "2_P$2") (pintype "passive"))
      (node (ref "LED3") (pin "A") (pinfunction "A_A") (pintype "passive"))
      (node (ref "R1") (pin "2") (pinfunction "2_2") (pintype "passive"))
      (node (ref "R45") (pin "2") (pinfunction "2_2") (pintype "passive"))
      (node (ref "R51") (pin "2") (pinfunction "2_2") (pintype "passive"))
      (node (ref "R52") (pin "2") (pinfunction "2_2") (pintype "passive"))
      (node (ref "R53") (pin "2") (pinfunction "2_2") (pintype "passive"))
    )
    (net (code "3") (name "+12V") (class "Default")
      (node (ref "C30") (pin "1") (pinfunction "1_1") (pintype "passive"))
      (node (ref "C9") (pin "1") (pinfunction "1_1") (pintype "passive"))
      (node (ref "D2") (pin "C") (pinfunction "C_C") (pintype "passive"))
      (node (ref "F2") (pin "2A") (pinfunction "2A_2A") (pintype "passive"))
      (node (ref "F2") (pin "2B") (pinfunction "2B_2B") (pintype "passive"))
      (node (ref "F3") (pin "2A") (pinfunction "2A_2A") (pintype "passive"))
      (node (ref "F3") (pin "2B") (pinfunction "2B_2B") (pintype "passive"))
      (node (ref "IC2") (pin "3") (pinfunction "VIN_3") (pintype "power_in"))
      (node (ref "IC2") (pin "5") (pinfunction "EN_5") (pintype "input"))
      (node (ref "LED4") (pin "A") (pinfunction "A_A") (pintype "passive"))
    )
    (net (code "4") (name "ESTOP_ENG") (class "Default")
      (node (ref "IC3") (pin "42") (pinfunction "RD8_42") (pintype "bidirectional"))
      (node (ref "Q1") (pin "1") (pinfunction "G_1") (pintype "passive"))
      (node (ref "R67") (pin "1") (pinfunction "1_1") (pintype "passive"))
    )
    (net (code "5") (name "ESTOP_SNS") (class "Default")
      (node (ref "IC3") (pin "12") (pinfunction "RA11_12") (pintype "bidirectional"))
      (node (ref "R10") (pin "1") (pinfunction "1_1") (pintype "passive"))
      (node (ref "R9") (pin "2") (pinfunction "2_2") (pintype "passive"))
    )
    (net (code "6") (name "GND") (class "Default")
      (node (ref "C1") (pin "2") (pinfunction "2_2") (pintype "passive"))
      (node (ref "C10") (pin "2") (pinfunction "2_2") (pintype "passive"))
      (node (ref "C11") (pin "2") (pinfunction "2_2") (pintype "passive"))
      (node (ref "C12") (pin "2") (pinfunction "2_2") (pintype "passive"))
      (node (ref "C13") (pin "2") (pinfunction "2_2") (pintype "passive"))
      (node (ref "C14") (pin "2") (pinfunction "2_2") (pintype "passive"))
      (node (ref "C16") (pin "2") (pinfunction "2_2") (pintype "passive"))
      (node (ref "C17") (pin "2") (pinfunction "2_2") (pintype "passive"))
      (node (ref "C18") (pin "2") (pinfunction "2_2") (pintype "passive"))
      (node (ref "C19") (pin "2") (pinfunction "2_2") (pintype "passive"))
      (node (ref "C2") (pin "2") (pinfunction "2_2") (pintype "passive"))
      (node (ref "C20") (pin "2") (pinfunction "2_2") (pintype "passive"))
      (node (ref "C21") (pin "2") (pinfunction "2_2") (pintype "passive"))
      (node (ref "C22") (pin "2") (pinfunction "2_2") (pintype "passive"))
      (node (ref "C23") (pin "2") (pinfunction "2_2") (pintype "passive"))
      (node (ref "C24") (pin "2") (pinfunction "2_2") (pintype "passive"))
      (node (ref "C25") (pin "2") (pinfunction "2_2") (pintype "passive"))
      (node (ref "C28") (pin "2") (pinfunction "2_2") (pintype "passive"))
      (node (ref "C29") (pin "2") (pinfunction "2_2") (pintype "passive"))
      (node (ref "C3") (pin "2") (pinfunction "2_2") (pintype "passive"))
      (node (ref "C30") (pin "2") (pinfunction "2_2") (pintype "passive"))
      (node (ref "C34") (pin "2") (pinfunction "2_2") (pintype "passive"))
      (node (ref "C4") (pin "2") (pinfunction "2_2") (pintype "passive"))
      (node (ref "C5") (pin "2") (pinfunction "2_2") (pintype "passive"))
      (node (ref "C6") (pin "2") (pinfunction "2_2") (pintype "passive"))
      (node (ref "C7") (pin "2") (pinfunction "2_2") (pintype "passive"))
      (node (ref "C9") (pin "2") (pinfunction "2_2") (pintype "passive"))
      (node (ref "D1") (pin "A") (pinfunction "A_A") (pintype "passive"))
      (node (ref "D2") (pin "A") (pinfunction "A_A") (pintype "passive"))
      (node (ref "D3") (pin "A") (pinfunction "A_A") (pintype "passive"))
      (node (ref "E1") (pin "9") (pinfunction "G_9") (pintype "power_in"))
      (node (ref "E2") (pin "9") (pinfunction "G_9") (pintype "power_in"))
      (node (ref "IC1") (pin "1") (pinfunction "ADJ_1") (pintype "input"))
      (node (ref "IC2") (pin "1") (pinfunction "GND_1") (pintype "power_in"))
      (node (ref "IC3") (pin "20") (pinfunction "AVSS_20") (pintype "power_in"))
      (node (ref "IC3") (pin "25") (pinfunction "VSS_25") (pintype "power_in"))
      (node (ref "IC3") (pin "41") (pinfunction "VSS_41") (pintype "power_in"))
      (node (ref "IC3") (pin "56") (pinfunction "VSS_56") (pintype "power_in"))
      (node (ref "IC3") (pin "9") (pinfunction "VSS_9") (pintype "power_in"))
      (node (ref "IC5") (pin "11") (pinfunction "VSSRX_11") (pintype "input"))
      (node (ref "IC5") (pin "18") (pinfunction "VSSTX_18") (pintype "input"))
      (node (ref "IC5") (pin "2") (pinfunction "VSS_2") (pintype "input"))
      (node (ref "IC5") (pin "21") (pinfunction "VSSPLL_21") (pintype "input"))
      (node (ref "IC5") (pin "22") (pinfunction "VSSOSC_22") (pintype "input"))
      (node (ref "J1") (pin "1") (pinfunction "1_1") (pintype "passive"))
      (node (ref "J10") (pin "1") (pinfunction "1_1") (pintype "passive"))
      (node (ref "J11") (pin "1") (pinfunction "1_1") (pintype "passive"))
      (node (ref "J12") (pin "2") (pinfunction "2_2") (pintype "passive"))
      (node (ref "J12") (pin "3") (pinfunction "2_3") (pintype "passive"))
      (node (ref "J12") (pin "4") (pinfunction "2_4") (pintype "passive"))
      (node (ref "J12") (pin "5") (pinfunction "2_5") (pintype "passive"))
      (node (ref "J13") (pin "5") (pinfunction "GND_5") (pintype "bidirectional"))
      (node (ref "J13") (pin "P$1") (pinfunction "SHIELD_P$1") (pintype "power_in"))
      (node (ref "J13") (pin "P$2") (pinfunction "SHIELD_P$2") (pintype "power_in"))
      (node (ref "J13") (pin "P$3") (pinfunction "SHIELD_P$3") (pintype "power_in"))
      (node (ref "J14") (pin "1") (pinfunction "1_1") (pintype "passive"))
      (node (ref "J15") (pin "1") (pinfunction "1_1") (pintype "passive"))
      (node (ref "J16") (pin "1") (pinfunction "1_1") (pintype "passive"))
      (node (ref "J17") (pin "1") (pinfunction "1_1") (pintype "passive"))
      (node (ref "J18") (pin "3") (pinfunction "B_3") (pintype "passive"))
      (node (ref "J18") (pin "5") (pinfunction "B_5") (pintype "passive"))
      (node (ref "J18") (pin "9") (pinfunction "B_9") (pintype "passive"))
      (node (ref "J2") (pin "1") (pinfunction "1_1") (pintype "passive"))
      (node (ref "J20") (pin "1") (pinfunction "1_1") (pintype "passive"))
      (node (ref "J21") (pin "1") (pinfunction "1_1") (pintype "passive"))
      (node (ref "J22") (pin "1") (pinfunction "1_1") (pintype "passive"))
      (node (ref "J24") (pin "1") (pinfunction "1_1") (pintype "passive"))
      (node (ref "J25") (pin "1") (pinfunction "1_1") (pintype "passive"))
      (node (ref "J26") (pin "1") (pinfunction "1_1") (pintype "passive"))
      (node (ref "J27") (pin "1") (pinfunction "1_1") (pintype "passive"))
      (node (ref "J3") (pin "2") (pinfunction "2_2") (pintype "passive"))
      (node (ref "J6") (pin "1") (pinfunction "1_1") (pintype "passive"))
      (node (ref "J8") (pin "3") (pinfunction "3_3") (pintype "passive"))
      (node (ref "J9") (pin "1") (pinfunction "1_1") (pintype "passive"))
      (node (ref "LED6") (pin "C") (pinfunction "C_C") (pintype "passive"))
      (node (ref "LED7") (pin "C") (pinfunction "C_C") (pintype "passive"))
      (node (ref "LED8") (pin "C") (pinfunction "C_C") (pintype "passive"))
      (node (ref "LED9") (pin "C") (pinfunction "C_C") (pintype "passive"))
      (node (ref "Q1") (pin "2") (pinfunction "S_2") (pintype "passive"))
      (node (ref "R10") (pin "2") (pinfunction "2_2") (pintype "passive"))
      (node (ref "R13") (pin "2") (pinfunction "2_2") (pintype "passive"))
      (node (ref "R2") (pin "1") (pinfunction "1_1") (pintype "passive"))
      (node (ref "R4") (pin "2") (pinfunction "2_2") (pintype "passive"))
      (node (ref "R5") (pin "2") (pinfunction "2_2") (pintype "passive"))
      (node (ref "R50") (pin "1") (pinfunction "1_1") (pintype "passive"))
      (node (ref "R6") (pin "2") (pinfunction "2_2") (pintype "passive"))
      (node (ref "R67") (pin "2") (pinfunction "2_2") (pintype "passive"))
      (node (ref "R68") (pin "2") (pinfunction "2_2") (pintype "passive"))
      (node (ref "R7") (pin "2") (pinfunction "2_2") (pintype "passive"))
      (node (ref "R8") (pin "2") (pinfunction "2_2") (pintype "passive"))
      (node (ref "U1") (pin "P$2") (pinfunction "GND_P$2") (pintype "power_in"))
      (node (ref "XO1") (pin "2") (pinfunction "GND_2") (pintype "power_in"))
    )
    (net (code "7") (name "GPIO_0") (class "Default")
      (node (ref "IC3") (pin "4") (pinfunction "RG6_4") (pintype "bidirectional"))
      (node (ref "R46") (pin "2") (pinfunction "2_2") (pintype "passive"))
    )
    (net (code "8") (name "GPIO_1") (class "Default")
      (node (ref "IC3") (pin "5") (pinfunction "RG7_5") (pintype "bidirectional"))
      (node (ref "R47") (pin "2") (pinfunction "2_2") (pintype "passive"))
    )
    (net (code "9") (name "GPIO_2") (class "Default")
      (node (ref "IC3") (pin "6") (pinfunction "RG8_6") (pintype "bidirectional"))
      (node (ref "R48") (pin "2") (pinfunction "2_2") (pintype "passive"))
    )
    (net (code "10") (name "GPIO_3") (class "Default")
      (node (ref "IC3") (pin "8") (pinfunction "RG9_8") (pintype "bidirectional"))
      (node (ref "R49") (pin "2") (pinfunction "2_2") (pintype "passive"))
    )
    (net (code "11") (name "M1FB") (class "Default")
      (node (ref "IC3") (pin "3") (pinfunction "RB15_3") (pintype "bidirectional"))
      (node (ref "R20") (pin "2") (pinfunction "2_2") (pintype "passive"))
    )
    (net (code "12") (name "M1RC") (class "Default")
      (node (ref "IC3") (pin "2") (pinfunction "RB14_2") (pintype "bidirectional"))
      (node (ref "R19") (pin "2") (pinfunction "2_2") (pintype "passive"))
    )
    (net (code "13") (name "M2FB") (class "Default")
      (node (ref "IC3") (pin "60") (pinfunction "RB10_60") (pintype "bidirectional"))
      (node (ref "R38") (pin "2") (pinfunction "2_2") (pintype "passive"))
    )
    (net (code "14") (name "M2RC") (class "Default")
      (node (ref "IC3") (pin "59") (pinfunction "RF1_59") (pintype "bidirectional"))
      (node (ref "R34") (pin "2") (pinfunction "2_2") (pintype "passive"))
    )
    (net (code "15") (name "M3FB") (class "Default")
      (node (ref "IC3") (pin "48") (pinfunction "RB8_48") (pintype "bidirectional"))
      (node (ref "R42") (pin "2") (pinfunction "2_2") (pintype "passive"))
    )
    (net (code "16") (name "M3RC") (class "Default")
      (node (ref "IC3") (pin "47") (pinfunction "RC13_47") (pintype "bidirectional"))
      (node (ref "R41") (pin "2") (pinfunction "2_2") (pintype "passive"))
    )
    (net (code "17") (name "M4FB") (class "Default")
      (node (ref "IC3") (pin "46") (pinfunction "RB7_46") (pintype "bidirectional"))
      (node (ref "R56") (pin "2") (pinfunction "2_2") (pintype "passive"))
    )
    (net (code "18") (name "M4RC") (class "Default")
      (node (ref "IC3") (pin "45") (pinfunction "RC10_45") (pintype "bidirectional"))
      (node (ref "R55") (pin "2") (pinfunction "2_2") (pintype "passive"))
    )
    (net (code "19") (name "MISO") (class "Default")
      (node (ref "IC3") (pin "18") (pinfunction "RB3_18") (pintype "bidirectional"))
      (node (ref "IC5") (pin "6") (pinfunction "SO_6") (pintype "output"))
      (node (ref "U1") (pin "P$14") (pinfunction "MISO_P$14") (pintype "output"))
    )
    (net (code "20") (name "MOSI") (class "Default")
      (node (ref "IC3") (pin "21") (pinfunction "RC0_21") (pintype "bidirectional"))
      (node (ref "IC5") (pin "7") (pinfunction "SI_7") (pintype "input"))
      (node (ref "U1") (pin "P$15") (pinfunction "MOSI_P$15") (pintype "input"))
    )
    (net (code "21") (name "Net-(C19-Pad1)") (class "Default")
      (node (ref "C19") (pin "1") (pinfunction "1_1") (pintype "passive"))
      (node (ref "R14") (pin "2") (pinfunction "2_2") (pintype "passive"))
      (node (ref "R17") (pin "2") (pinfunction "2_2") (pintype "passive"))
    )
    (net (code "22") (name "Net-(C28-Pad1)") (class "Default")
      (node (ref "C28") (pin "1") (pinfunction "1_1") (pintype "passive"))
      (node (ref "C29") (pin "1") (pinfunction "1_1") (pintype "passive"))
      (node (ref "FB1") (pin "2") (pinfunction "2_2") (pintype "passive"))
      (node (ref "J24") (pin "2") (pinfunction "2_2") (pintype "passive"))
      (node (ref "J25") (pin "2") (pinfunction "2_2") (pintype "passive"))
      (node (ref "J26") (pin "2") (pinfunction "2_2") (pintype "passive"))
      (node (ref "J27") (pin "2") (pinfunction "2_2") (pintype "passive"))
    )
    (net (code "23") (name "Net-(C34-Pad1)") (class "Default")
      (node (ref "C34") (pin "1") (pinfunction "1_1") (pintype "passive"))
      (node (ref "R29") (pin "2") (pinfunction "2_2") (pintype "passive"))
      (node (ref "R30") (pin "2") (pinfunction "2_2") (pintype "passive"))
      (node (ref "R31") (pin "2") (pinfunction "2_2") (pintype "passive"))
      (node (ref "R32") (pin "2") (pinfunction "2_2") (pintype "passive"))
    )
    (net (code "24") (name "Net-(E1-O1)") (class "Default")
      (node (ref "E1") (pin "8") (pinfunction "O1_8") (pintype "bidirectional"))
      (node (ref "J8") (pin "5") (pinfunction "5_5") (pintype "passive"))
    )
    (net (code "25") (name "Net-(E1-O2)") (class "Default")
      (node (ref "E1") (pin "7") (pinfunction "O2_7") (pintype "bidirectional"))
      (node (ref "J8") (pin "4") (pinfunction "4_4") (pintype "passive"))
    )
    (net (code "26") (name "Net-(F1-1-Pad1A)") (class "Default")
      (node (ref "F1") (pin "1A") (pinfunction "1_1A") (pintype "passive"))
      (node (ref "F1") (pin "1B") (pinfunction "1_1B") (pintype "passive"))
      (node (ref "J1") (pin "2") (pinfunction "2_2") (pintype "passive"))
    )
    (net (code "27") (name "Net-(F3-Pad1A)") (class "Default")
      (node (ref "F3") (pin "1A") (pinfunction "1A_1A") (pintype "passive"))
      (node (ref "F3") (pin "1B") (pinfunction "1B_1B") (pintype "passive"))
      (node (ref "J3") (pin "3") (pinfunction "3_3") (pintype "passive"))
    )
    (net (code "28") (name "Net-(IC2-SW)") (class "Default")
      (node (ref "C8") (pin "2") (pinfunction "2_2") (pintype "passive"))
      (node (ref "IC2") (pin "2") (pinfunction "SW_2") (pintype "output"))
      (node (ref "L1") (pin "P$1") (pinfunction "1_P$1") (pintype "passive"))
    )
    (net (code "29") (name "Net-(IC2-VBST)") (class "Default")
      (node (ref "C8") (pin "1") (pinfunction "1_1") (pintype "passive"))
      (node (ref "IC2") (pin "6") (pinfunction "VBST_6") (pintype "passive"))
    )
    (net (code "30") (name "Net-(IC2-VFB)") (class "Default")
      (node (ref "IC2") (pin "4") (pinfunction "VFB_4") (pintype "input"))
      (node (ref "R1") (pin "1") (pinfunction "1_1") (pintype "passive"))
      (node (ref "R2") (pin "2") (pinfunction "2_2") (pintype "passive"))
    )
    (net (code "31") (name "Net-(IC3-D+)") (class "Default")
      (node (ref "IC3") (pin "37") (pinfunction "D+_37") (pintype "bidirectional"))
      (node (ref "J13") (pin "3") (pinfunction "D+_3") (pintype "bidirectional"))
    )
    (net (code "32") (name "Net-(IC3-D-)") (class "Default")
      (node (ref "IC3") (pin "36") (pinfunction "D-_36") (pintype "bidirectional"))
      (node (ref "J13") (pin "2") (pinfunction "D-_2") (pintype "bidirectional"))
    )
    (net (code "33") (name "Net-(IC3-OSCI{slash}RC12)") (class "Default")
      (node (ref "IC3") (pin "39") (pinfunction "OSCI/RC12_39") (pintype "bidirectional"))
      (node (ref "XO1") (pin "3") (pinfunction "OUT_3") (pintype "output"))
    )
    (net (code "34") (name "Net-(IC3-VBUS)") (class "Default")
      (node (ref "C25") (pin "1") (pinfunction "1_1") (pintype "passive"))
      (node (ref "IC3") (pin "34") (pinfunction "VBUS_34") (pintype "power_in"))
      (node (ref "J13") (pin "1") (pinfunction "VBUS_1") (pintype "bidirectional"))
    )
    (net (code "35") (name "Net-(IC5-LEDA)") (class "Default")
      (node (ref "IC5") (pin "27") (pinfunction "LEDA_27") (pintype "output"))
      (node (ref "R11") (pin "1") (pinfunction "1_1") (pintype "passive"))
    )
    (net (code "36") (name "Net-(IC5-LEDB)") (class "Default")
      (node (ref "IC5") (pin "26") (pinfunction "LEDB_26") (pintype "output"))
      (node (ref "R12") (pin "1") (pinfunction "1_1") (pintype "passive"))
    )
    (net (code "37") (name "Net-(IC5-OSC1)") (class "Default")
      (node (ref "C17") (pin "1") (pinfunction "1_1") (pintype "passive"))
      (node (ref "IC5") (pin "23") (pinfunction "OSC1_23") (pintype "input"))
      (node (ref "X1") (pin "1") (pinfunction "1_1") (pintype "passive"))
    )
    (net (code "38") (name "Net-(IC5-OSC2)") (class "Default")
      (node (ref "C18") (pin "1") (pinfunction "1_1") (pintype "passive"))
      (node (ref "IC5") (pin "24") (pinfunction "OSC2_24") (pintype "output"))
      (node (ref "X1") (pin "2") (pinfunction "2_2") (pintype "passive"))
    )
    (net (code "39") (name "Net-(IC5-RBIAS)") (class "Default")
      (node (ref "IC5") (pin "14") (pinfunction "RBIAS_14") (pintype "input"))
      (node (ref "R13") (pin "1") (pinfunction "1_1") (pintype "passive"))
    )
    (net (code "40") (name "Net-(IC5-TPIN+)") (class "Default")
      (node (ref "IC5") (pin "13") (pinfunction "TPIN+_13") (pintype "input"))
      (node (ref "R17") (pin "1") (pinfunction "1_1") (pintype "passive"))
      (node (ref "T1") (pin "6") (pinfunction "6_6") (pintype "passive"))
    )
    (net (code "41") (name "Net-(IC5-TPIN-)") (class "Default")
      (node (ref "IC5") (pin "12") (pinfunction "TPIN-_12") (pintype "input"))
      (node (ref "R14") (pin "1") (pinfunction "1_1") (pintype "passive"))
      (node (ref "T1") (pin "8") (pinfunction "8_8") (pintype "passive"))
    )
    (net (code "42") (name "Net-(IC5-TPOUT+)") (class "Default")
      (node (ref "IC5") (pin "17") (pinfunction "TPOUT+_17") (pintype "output"))
      (node (ref "R15") (pin "1") (pinfunction "1_1") (pintype "passive"))
      (node (ref "T1") (pin "1") (pinfunction "1_1") (pintype "passive"))
    )
    (net (code "43") (name "Net-(IC5-TPOUT-)") (class "Default")
      (node (ref "IC5") (pin "16") (pinfunction "TPOUT-_16") (pintype "output"))
      (node (ref "R16") (pin "1") (pinfunction "1_1") (pintype "passive"))
      (node (ref "T1") (pin "3") (pinfunction "3_3") (pintype "passive"))
    )
    (net (code "44") (name "Net-(IC5-VCAP)") (class "Default")
      (node (ref "C16") (pin "1") (pinfunction "1_1") (pintype "passive"))
      (node (ref "IC5") (pin "1") (pinfunction "VCAP_1") (pintype "input"))
    )
    (net (code "45") (name "Net-(J2-Pad2)") (class "Default")
      (node (ref "J2") (pin "2") (pinfunction "2_2") (pintype "passive"))
      (node (ref "R21") (pin "1") (pinfunction "1_1") (pintype "passive"))
      (node (ref "R39") (pin "1") (pinfunction "1_1") (pintype "passive"))
    )
    (net (code "46") (name "Net-(J4-P$1)") (class "Default")
      (node (ref "J4") (pin "1") (pinfunction "P$1_1") (pintype "passive"))
      (node (ref "Q2") (pin "2") (pinfunction "S_2") (pintype "passive"))
      (node (ref "R66") (pin "1") (pinfunction "1_1") (pintype "passive"))
    )
    (net (code "47") (name "Net-(J4-P$2)") (class "Default")
      (node (ref "F2") (pin "1A") (pinfunction "1A_1A") (pintype "passive"))
      (node (ref "F2") (pin "1B") (pinfunction "1B_1B") (pintype "passive"))
      (node (ref "J4") (pin "2") (pinfunction "P$2_2") (pintype "passive"))
    )
    (net (code "48") (name "Net-(J6-Pad2)") (class "Default")
      (node (ref "J6") (pin "2") (pinfunction "2_2") (pintype "passive"))
      (node (ref "R18") (pin "2") (pinfunction "2_2") (pintype "passive"))
      (node (ref "R20") (pin "1") (pinfunction "1_1") (pintype "passive"))
    )
    (net (code "49") (name "Net-(J6-Pad3)") (class "Default")
      (node (ref "J6") (pin "3") (pinfunction "3_3") (pintype "passive"))
      (node (ref "R19") (pin "1") (pinfunction "1_1") (pintype "passive"))
    )
    (net (code "50") (name "Net-(J7-Pad1)") (class "Default")
      (node (ref "J7") (pin "1") (pinfunction "1_1") (pintype "passive"))
      (node (ref "T1") (pin "16") (pinfunction "16_16") (pintype "passive"))
    )
    (net (code "51") (name "Net-(J7-Pad2)") (class "Default")
      (node (ref "J7") (pin "2") (pinfunction "2_2") (pintype "passive"))
      (node (ref "T1") (pin "14") (pinfunction "14_14") (pintype "passive"))
    )
    (net (code "52") (name "Net-(J7-Pad3)") (class "Default")
      (node (ref "J7") (pin "3") (pinfunction "3_3") (pintype "passive"))
      (node (ref "T1") (pin "11") (pinfunction "11_11") (pintype "passive"))
    )
    (net (code "53") (name "Net-(J7-Pad4)") (class "Default")
      (node (ref "J7") (pin "4") (pinfunction "4_4") (pintype "passive"))
      (node (ref "J7") (pin "5") (pinfunction "5_5") (pintype "passive"))
      (node (ref "R31") (pin "1") (pinfunction "1_1") (pintype "passive"))
    )
    (net (code "54") (name "Net-(J7-Pad6)") (class "Default")
      (node (ref "J7") (pin "6") (pinfunction "6_6") (pintype "passive"))
      (node (ref "T1") (pin "9") (pinfunction "9_9") (pintype "passive"))
    )
    (net (code "55") (name "Net-(J7-Pad7)") (class "Default")
      (node (ref "J7") (pin "7") (pinfunction "7_7") (pintype "passive"))
      (node (ref "J7") (pin "8") (pinfunction "8_8") (pintype "passive"))
      (node (ref "R32") (pin "1") (pinfunction "1_1") (pintype "passive"))
    )
    (net (code "56") (name "Net-(J9-Pad2)") (class "Default")
      (node (ref "J9") (pin "2") (pinfunction "2_2") (pintype "passive"))
      (node (ref "R33") (pin "2") (pinfunction "2_2") (pintype "passive"))
      (node (ref "R38") (pin "1") (pinfunction "1_1") (pintype "passive"))
    )
    (net (code "57") (name "Net-(J9-Pad3)") (class "Default")
      (node (ref "J9") (pin "3") (pinfunction "3_3") (pintype "passive"))
      (node (ref "R34") (pin "1") (pinfunction "1_1") (pintype "passive"))
    )
    (net (code "58") (name "Net-(J10-Pad2)") (class "Default")
      (node (ref "J10") (pin "2") (pinfunction "2_2") (pintype "passive"))
      (node (ref "R40") (pin "2") (pinfunction "2_2") (pintype "passive"))
      (node (ref "R42") (pin "1") (pinfunction "1_1") (pintype "passive"))
    )
    (net (code "59") (name "Net-(J10-Pad3)") (class "Default")
      (node (ref "J10") (pin "3") (pinfunction "3_3") (pintype "passive"))
      (node (ref "R41") (pin "1") (pinfunction "1_1") (pintype "passive"))
    )
    (net (code "60") (name "Net-(J11-Pad2)") (class "Default")
      (node (ref "J11") (pin "2") (pinfunction "2_2") (pintype "passive"))
      (node (ref "R54") (pin "2") (pinfunction "2_2") (pintype "passive"))
      (node (ref "R56") (pin "1") (pinfunction "1_1") (pintype "passive"))
    )
    (net (code "61") (name "Net-(J11-Pad3)") (class "Default")
      (node (ref "J11") (pin "3") (pinfunction "3_3") (pintype "passive"))
      (node (ref "R55") (pin "1") (pinfunction "1_1") (pintype "passive"))
    )
    (net (code "62") (name "Net-(J14-Pad2)") (class "Default")
      (node (ref "J14") (pin "2") (pinfunction "2_2") (pintype "passive"))
      (node (ref "R36") (pin "1") (pinfunction "1_1") (pintype "passive"))
    )
    (net (code "63") (name "Net-(J14-Pad3)") (class "Default")
      (node (ref "J14") (pin "3") (pinfunction "3_3") (pintype "passive"))
      (node (ref "R35") (pin "1") (pinfunction "1_1") (pintype "passive"))
    )
    (net (code "64") (name "Net-(J14-Pad4)") (class "Default")
      (node (ref "J14") (pin "4") (pinfunction "4_4") (pintype "passive"))
      (node (ref "R45") (pin "1") (pinfunction "1_1") (pintype "passive"))
    )
    (net (code "65") (name "Net-(J14-Pad5)") (class "Default")
      (node (ref "J14") (pin "5") (pinfunction "5_5") (pintype "passive"))
      (node (ref "R23") (pin "1") (pinfunction "1_1") (pintype "passive"))
    )
    (net (code "66") (name "Net-(J15-Pad2)") (class "Default")
      (node (ref "J15") (pin "2") (pinfunction "2_2") (pintype "passive"))
      (node (ref "R59") (pin "1") (pinfunction "1_1") (pintype "passive"))
    )
    (net (code "67") (name "Net-(J15-Pad3)") (class "Default")
      (node (ref "J15") (pin "3") (pinfunction "3_3") (pintype "passive"))
      (node (ref "R58") (pin "1") (pinfunction "1_1") (pintype "passive"))
    )
    (net (code "68") (name "Net-(J15-Pad4)") (class "Default")
      (node (ref "J15") (pin "4") (pinfunction "4_4") (pintype "passive"))
      (node (ref "R51") (pin "1") (pinfunction "1_1") (pintype "passive"))
    )
    (net (code "69") (name "Net-(J15-Pad5)") (class "Default")
      (node (ref "J15") (pin "5") (pinfunction "5_5") (pintype "passive"))
      (node (ref "R57") (pin "1") (pinfunction "1_1") (pintype "passive"))
    )
    (net (code "70") (name "Net-(J16-Pad2)") (class "Default")
      (node (ref "J16") (pin "2") (pinfunction "2_2") (pintype "passive"))
      (node (ref "R62") (pin "1") (pinfunction "1_1") (pintype "passive"))
    )
    (net (code "71") (name "Net-(J16-Pad3)") (class "Default")
      (node (ref "J16") (pin "3") (pinfunction "3_3") (pintype "passive"))
      (node (ref "R61") (pin "1") (pinfunction "1_1") (pintype "passive"))
    )
    (net (code "72") (name "Net-(J16-Pad4)") (class "Default")
      (node (ref "J16") (pin "4") (pinfunction "4_4") (pintype "passive"))
      (node (ref "R52") (pin "1") (pinfunction "1_1") (pintype "passive"))
    )
    (net (code "73") (name "Net-(J16-Pad5)") (class "Default")
      (node (ref "J16") (pin "5") (pinfunction "5_5") (pintype "passive"))
      (node (ref "R60") (pin "1") (pinfunction "1_1") (pintype "passive"))
    )
    (net (code "74") (name "Net-(J17-Pad2)") (class "Default")
      (node (ref "J17") (pin "2") (pinfunction "2_2") (pintype "passive"))
      (node (ref "R65") (pin "1") (pinfunction "1_1") (pintype "passive"))
    )
    (net (code "75") (name "Net-(J17-Pad3)") (class "Default")
      (node (ref "J17") (pin "3") (pinfunction "3_3") (pintype "passive"))
      (node (ref "R64") (pin "1") (pinfunction "1_1") (pintype "passive"))
    )
    (net (code "76") (name "Net-(J17-Pad4)") (class "Default")
      (node (ref "J17") (pin "4") (pinfunction "4_4") (pintype "passive"))
      (node (ref "R53") (pin "1") (pinfunction "1_1") (pintype "passive"))
    )
    (net (code "77") (name "Net-(J17-Pad5)") (class "Default")
      (node (ref "J17") (pin "5") (pinfunction "5_5") (pintype "passive"))
      (node (ref "R63") (pin "1") (pinfunction "1_1") (pintype "passive"))
    )
    (net (code "78") (name "Net-(J20-Pad2)") (class "Default")
      (node (ref "J20") (pin "2") (pinfunction "2_2") (pintype "passive"))
      (node (ref "R22") (pin "1") (pinfunction "1_1") (pintype "passive"))
      (node (ref "R24") (pin "1") (pinfunction "1_1") (pintype "passive"))
    )
    (net (code "79") (name "Net-(J21-Pad2)") (class "Default")
      (node (ref "J21") (pin "2") (pinfunction "2_2") (pintype "passive"))
      (node (ref "R25") (pin "1") (pinfunction "1_1") (pintype "passive"))
      (node (ref "R26") (pin "1") (pinfunction "1_1") (pintype "passive"))
    )
    (net (code "80") (name "Net-(J22-Pad2)") (class "Default")
      (node (ref "J22") (pin "2") (pinfunction "2_2") (pintype "passive"))
      (node (ref "R27") (pin "1") (pinfunction "1_1") (pintype "passive"))
      (node (ref "R28") (pin "1") (pinfunction "1_1") (pintype "passive"))
    )
    (net (code "81") (name "Net-(J24-Pad3)") (class "Default")
      (node (ref "J24") (pin "3") (pinfunction "3_3") (pintype "passive"))
      (node (ref "R46") (pin "1") (pinfunction "1_1") (pintype "passive"))
    )
    (net (code "82") (name "Net-(J25-Pad3)") (class "Default")
      (node (ref "J25") (pin "3") (pinfunction "3_3") (pintype "passive"))
      (node (ref "R47") (pin "1") (pinfunction "1_1") (pintype "passive"))
    )
    (net (code "83") (name "Net-(J26-Pad3)") (class "Default")
      (node (ref "J26") (pin "3") (pinfunction "3_3") (pintype "passive"))
      (node (ref "R48") (pin "1") (pinfunction "1_1") (pintype "passive"))
    )
    (net (code "84") (name "Net-(J27-Pad3)") (class "Default")
      (node (ref "J27") (pin "3") (pinfunction "3_3") (pintype "passive"))
      (node (ref "R49") (pin "1") (pinfunction "1_1") (pintype "passive"))
    )
    (net (code "85") (name "Net-(LED1-PadC)") (class "Default")
      (node (ref "LED1") (pin "C") (pinfunction "C_C") (pintype "passive"))
      (node (ref "R68") (pin "1") (pinfunction "1_1") (pintype "passive"))
    )
    (net (code "86") (name "Net-(LED2-PadC)") (class "Default")
      (node (ref "LED2") (pin "C") (pinfunction "C_C") (pintype "passive"))
      (node (ref "R5") (pin "1") (pinfunction "1_1") (pintype "passive"))
    )
    (net (code "87") (name "Net-(LED3-PadC)") (class "Default")
      (node (ref "LED3") (pin "C") (pinfunction "C_C") (pintype "passive"))
      (node (ref "R6") (pin "1") (pinfunction "1_1") (pintype "passive"))
    )
    (net (code "88") (name "Net-(LED4-PadC)") (class "Default")
      (node (ref "LED4") (pin "C") (pinfunction "C_C") (pintype "passive"))
      (node (ref "R4") (pin "1") (pinfunction "1_1") (pintype "passive"))
    )
    (net (code "89") (name "Net-(LED5-PadC)") (class "Default")
      (node (ref "LED5") (pin "C") (pinfunction "C_C") (pintype "passive"))
      (node (ref "R7") (pin "1") (pinfunction "1_1") (pintype "passive"))
    )
    (net (code "90") (name "Net-(LED6-PadA)") (class "Default")
      (node (ref "LED6") (pin "A") (pinfunction "A_A") (pintype "passive"))
      (node (ref "R12") (pin "2") (pinfunction "2_2") (pintype "passive"))
    )
    (net (code "91") (name "Net-(LED7-PadA)") (class "Default")
      (node (ref "LED7") (pin "A") (pinfunction "A_A") (pintype "passive"))
      (node (ref "R11") (pin "2") (pinfunction "2_2") (pintype "passive"))
    )
    (net (code "92") (name "Net-(LED8-PadA)") (class "Default")
      (node (ref "LED8") (pin "A") (pinfunction "A_A") (pintype "passive"))
      (node (ref "R37") (pin "1") (pinfunction "1_1") (pintype "passive"))
    )
    (net (code "93") (name "Net-(LED9-PadA)") (class "Default")
      (node (ref "LED9") (pin "A") (pinfunction "A_A") (pintype "passive"))
      (node (ref "R43") (pin "1") (pinfunction "1_1") (pintype "passive"))
    )
    (net (code "94") (name "Net-(Q1-D)") (class "Default")
      (node (ref "Q1") (pin "3") (pinfunction "D_3") (pintype "passive"))
      (node (ref "Q2") (pin "1") (pinfunction "G_1") (pintype "passive"))
      (node (ref "R66") (pin "2") (pinfunction "2_2") (pintype "passive"))
    )
    (net (code "95") (name "Net-(Q2-D)") (class "Default")
      (node (ref "D1") (pin "C") (pinfunction "C_C") (pintype "passive"))
      (node (ref "J5") (pin "A1") (pinfunction "1_A1") (pintype "passive"))
      (node (ref "J5") (pin "A2") (pinfunction "1_A2") (pintype "passive"))
      (node (ref "LED1") (pin "A") (pinfunction "A_A") (pintype "passive"))
      (node (ref "Q2") (pin "3") (pinfunction "D_3") (pintype "passive"))
      (node (ref "R9") (pin "1") (pinfunction "1_1") (pintype "passive"))
    )
    (net (code "96") (name "Net-(R29-Pad1)") (class "Default")
      (node (ref "R29") (pin "1") (pinfunction "1_1") (pintype "passive"))
      (node (ref "T1") (pin "15") (pinfunction "15_15") (pintype "passive"))
    )
    (net (code "97") (name "Net-(R30-Pad1)") (class "Default")
      (node (ref "R30") (pin "1") (pinfunction "1_1") (pintype "passive"))
      (node (ref "T1") (pin "10") (pinfunction "10_10") (pintype "passive"))
    )
    (net (code "98") (name "Net-(U1-ANT)") (class "Default")
      (node (ref "J12") (pin "1") (pinfunction "1_1") (pintype "passive"))
      (node (ref "U1") (pin "P$1") (pinfunction "ANT_P$1") (pintype "passive"))
    )
    (net (code "99") (name "Net-(U1-RESET)") (class "Default")
      (node (ref "R50") (pin "2") (pinfunction "2_2") (pintype "passive"))
      (node (ref "U1") (pin "P$12") (pinfunction "RESET_P$12") (pintype "input"))
    )
    (net (code "100") (name "PGC") (class "Default")
      (node (ref "E1") (pin "1") (pinfunction "I1_1") (pintype "bidirectional"))
      (node (ref "IC3") (pin "16") (pinfunction "RB1_16") (pintype "bidirectional"))
    )
    (net (code "101") (name "PGD") (class "Default")
      (node (ref "E1") (pin "2") (pinfunction "I2_2") (pintype "bidirectional"))
      (node (ref "IC3") (pin "15") (pinfunction "RB0_15") (pintype "bidirectional"))
    )
    (net (code "102") (name "QEA_1") (class "Default")
      (node (ref "IC3") (pin "62") (pinfunction "RB12_62") (pintype "bidirectional"))
      (node (ref "R35") (pin "2") (pinfunction "2_2") (pintype "passive"))
    )
    (net (code "103") (name "QEA_2") (class "Default")
      (node (ref "IC3") (pin "55") (pinfunction "RC9_55") (pintype "bidirectional"))
      (node (ref "R58") (pin "2") (pinfunction "2_2") (pintype "passive"))
    )
    (net (code "104") (name "QEA_3") (class "Default")
      (node (ref "IC3") (pin "52") (pinfunction "RC8_52") (pintype "bidirectional"))
      (node (ref "R61") (pin "2") (pinfunction "2_2") (pintype "passive"))
    )
    (net (code "105") (name "QEA_4") (class "Default")
      (node (ref "IC3") (pin "44") (pinfunction "RB6_44") (pintype "bidirectional"))
      (node (ref "R64") (pin "2") (pinfunction "2_2") (pintype "passive"))
    )
    (net (code "106") (name "QEB_1") (class "Default")
      (node (ref "IC3") (pin "63") (pinfunction "RB13_63") (pintype "bidirectional"))
      (node (ref "R23") (pin "2") (pinfunction "2_2") (pintype "passive"))
    )
    (net (code "107") (name "QEB_2") (class "Default")
      (node (ref "IC3") (pin "58") (pinfunction "RF0_58") (pintype "bidirectional"))
      (node (ref "R57") (pin "2") (pinfunction "2_2") (pintype "passive"))
    )
    (net (code "108") (name "QEB_3") (class "Default")
      (node (ref "IC3") (pin "53") (pinfunction "RD5_53") (pintype "bidirectional"))
      (node (ref "R60") (pin "2") (pinfunction "2_2") (pintype "passive"))
    )
    (net (code "109") (name "QEB_4") (class "Default")
      (node (ref "IC3") (pin "50") (pinfunction "RC6_50") (pintype "bidirectional"))
      (node (ref "R63") (pin "2") (pinfunction "2_2") (pintype "passive"))
    )
    (net (code "110") (name "QEI_1") (class "Default")
      (node (ref "IC3") (pin "61") (pinfunction "RB11_61") (pintype "bidirectional"))
      (node (ref "R36") (pin "2") (pinfunction "2_2") (pintype "passive"))
    )
    (net (code "111") (name "QEI_2") (class "Default")
      (node (ref "IC3") (pin "54") (pinfunction "RD6_54") (pintype "bidirectional"))
      (node (ref "R59") (pin "2") (pinfunction "2_2") (pintype "passive"))
    )
    (net (code "112") (name "QEI_3") (class "Default")
      (node (ref "IC3") (pin "51") (pinfunction "RC7_51") (pintype "bidirectional"))
      (node (ref "R62") (pin "2") (pinfunction "2_2") (pintype "passive"))
    )
    (net (code "113") (name "QEI_4") (class "Default")
      (node (ref "IC3") (pin "43") (pinfunction "RB5_43") (pintype "bidirectional"))
      (node (ref "R65") (pin "2") (pinfunction "2_2") (pintype "passive"))
    )
    (net (code "114") (name "RX_DONE") (class "Default")
      (node (ref "IC3") (pin "40") (pinfunction "OSCO/RC15_40") (pintype "bidirectional"))
      (node (ref "U1") (pin "P$6") (pinfunction "DIO0_P$6") (pintype "bidirectional"))
    )
    (net (code "115") (name "RX_SW") (class "Default")
      (node (ref "IC3") (pin "27") (pinfunction "RE12_27") (pintype "bidirectional"))
      (node (ref "U1") (pin "P$4") (pinfunction "RX_SWITCH_P$4") (pintype "input"))
    )
    (net (code "116") (name "SCK") (class "Default")
      (node (ref "IC3") (pin "17") (pinfunction "RB2_17") (pintype "bidirectional"))
      (node (ref "IC5") (pin "8") (pinfunction "SCK_8") (pintype "input"))
      (node (ref "U1") (pin "P$13") (pinfunction "SCLK_P$13") (pintype "input"))
    )
    (net (code "117") (name "STAT1") (class "Default")
      (node (ref "IC3") (pin "22") (pinfunction "RC1_22") (pintype "bidirectional"))
      (node (ref "R37") (pin "2") (pinfunction "2_2") (pintype "passive"))
    )
    (net (code "118") (name "STAT2") (class "Default")
      (node (ref "IC3") (pin "23") (pinfunction "RC2_23") (pintype "bidirectional"))
      (node (ref "R43") (pin "2") (pinfunction "2_2") (pintype "passive"))
    )
    (net (code "119") (name "TCK") (class "Default")
      (node (ref "E2") (pin "3") (pinfunction "I3_3") (pintype "bidirectional"))
      (node (ref "IC3") (pin "1") (pinfunction "RA7_1") (pintype "bidirectional"))
    )
    (net (code "120") (name "TCKI") (class "Default")
      (node (ref "E2") (pin "6") (pinfunction "O3_6") (pintype "bidirectional"))
      (node (ref "J18") (pin "4") (pinfunction "B_4") (pintype "passive"))
    )
    (net (code "121") (name "TDI") (class "Default")
      (node (ref "E2") (pin "1") (pinfunction "I1_1") (pintype "bidirectional"))
      (node (ref "IC3") (pin "31") (pinfunction "RA8_31") (pintype "bidirectional"))
    )
    (net (code "122") (name "TDII") (class "Default")
      (node (ref "E2") (pin "8") (pinfunction "O1_8") (pintype "bidirectional"))
      (node (ref "J18") (pin "8") (pinfunction "B_8") (pintype "passive"))
    )
    (net (code "123") (name "TDO") (class "Default")
      (node (ref "E2") (pin "2") (pinfunction "I2_2") (pintype "bidirectional"))
      (node (ref "IC3") (pin "64") (pinfunction "RA10_64") (pintype "bidirectional"))
    )
    (net (code "124") (name "TDOI") (class "Default")
      (node (ref "E2") (pin "7") (pinfunction "O2_7") (pintype "bidirectional"))
      (node (ref "J18") (pin "6") (pinfunction "B_6") (pintype "passive"))
    )
    (net (code "125") (name "TH1") (class "Default")
      (node (ref "IC3") (pin "33") (pinfunction "RA4_33") (pintype "bidirectional"))
      (node (ref "R21") (pin "2") (pinfunction "2_2") (pintype "passive"))
    )
    (net (code "126") (name "TH2") (class "Default")
      (node (ref "IC3") (pin "28") (pinfunction "RE13_28") (pintype "bidirectional"))
      (node (ref "R24") (pin "2") (pinfunction "2_2") (pintype "passive"))
    )
    (net (code "127") (name "TH3") (class "Default")
      (node (ref "IC3") (pin "29") (pinfunction "RE14_29") (pintype "bidirectional"))
      (node (ref "R26") (pin "2") (pinfunction "2_2") (pintype "passive"))
    )
    (net (code "128") (name "TH4") (class "Default")
      (node (ref "IC3") (pin "30") (pinfunction "RE15_30") (pintype "bidirectional"))
      (node (ref "R28") (pin "2") (pinfunction "2_2") (pintype "passive"))
    )
    (net (code "129") (name "TMS") (class "Default")
      (node (ref "E2") (pin "4") (pinfunction "I4_4") (pintype "bidirectional"))
      (node (ref "IC3") (pin "49") (pinfunction "RB9_49") (pintype "bidirectional"))
    )
    (net (code "130") (name "TMSI") (class "Default")
      (node (ref "E2") (pin "5") (pinfunction "O4_5") (pintype "bidirectional"))
      (node (ref "J18") (pin "2") (pinfunction "B_2") (pintype "passive"))
    )
    (net (code "131") (name "TX_SW") (class "Default")
      (node (ref "IC3") (pin "32") (pinfunction "RB4_32") (pintype "bidirectional"))
      (node (ref "U1") (pin "P$5") (pinfunction "TX_SWITCH_P$5") (pintype "input"))
    )
    (net (code "132") (name "V+") (class "Default")
      (node (ref "J3") (pin "1") (pinfunction "1_1") (pintype "passive"))
      (node (ref "LED5") (pin "A") (pinfunction "A_A") (pintype "passive"))
      (node (ref "R3") (pin "1") (pinfunction "1_1") (pintype "passive"))
    )
    (net (code "133") (name "VBAT_SNS") (class "Default")
      (node (ref "IC3") (pin "11") (pinfunction "RA12_11") (pintype "bidirectional"))
      (node (ref "R3") (pin "2") (pinfunction "2_2") (pintype "passive"))
      (node (ref "R8") (pin "1") (pinfunction "1_1") (pintype "passive"))
    )
    (net (code "134") (name "VCCIO") (class "Default")
      (node (ref "FB1") (pin "1") (pinfunction "1_1") (pintype "passive"))
      (node (ref "J1") (pin "3") (pinfunction "3_3") (pintype "passive"))
    )
    (net (code "135") (name "unconnected-(E1-I3-Pad3)") (class "Default")
      (node (ref "E1") (pin "3") (pinfunction "I3_3") (pintype "bidirectional"))
    )
    (net (code "136") (name "unconnected-(E1-O3-Pad6)") (class "Default")
      (node (ref "E1") (pin "6") (pinfunction "O3_6") (pintype "bidirectional"))
    )
    (net (code "137") (name "unconnected-(IC5-CLKOUT-Pad3)") (class "Default")
      (node (ref "IC5") (pin "3") (pinfunction "CLKOUT_3") (pintype "output"))
    )
    (net (code "138") (name "unconnected-(IC5-NC*-Pad5)") (class "Default")
      (node (ref "IC5") (pin "5") (pinfunction "NC*_5") (pintype "output"))
    )
    (net (code "139") (name "unconnected-(J13-USBID-Pad4)") (class "Default")
      (node (ref "J13") (pin "4") (pinfunction "USBID_4") (pintype "bidirectional"))
    )
    (net (code "140") (name "unconnected-(J18H-B-Pad7)") (class "Default")
      (node (ref "J18") (pin "7") (pinfunction "B_7") (pintype "passive"))
    )
    (net (code "141") (name "unconnected-(T1-Pad7)") (class "Default")
      (node (ref "T1") (pin "7") (pinfunction "7_7") (pintype "passive"))
    )
    (net (code "142") (name "unconnected-(U1-DIO1-PadP$7)") (class "Default")
      (node (ref "U1") (pin "P$7") (pinfunction "DIO1_P$7") (pintype "bidirectional"))
    )
    (net (code "143") (name "unconnected-(U1-DIO2-PadP$8)") (class "Default")
      (node (ref "U1") (pin "P$8") (pinfunction "DIO2_P$8") (pintype "bidirectional"))
    )
    (net (code "144") (name "unconnected-(U1-DIO3-PadP$9)") (class "Default")
      (node (ref "U1") (pin "P$9") (pinfunction "DIO3_P$9") (pintype "bidirectional"))
    )
    (net (code "145") (name "unconnected-(U1-DIO4-PadP$10)") (class "Default")
      (node (ref "U1") (pin "P$10") (pinfunction "DIO4_P$10") (pintype "bidirectional"))
    )
    (net (code "146") (name "unconnected-(U1-DIO5-PadP$11)") (class "Default")
      (node (ref "U1") (pin "P$11") (pinfunction "DIO5_P$11") (pintype "bidirectional"))
    )
    (net (code "147") (name "unconnected-(XO1-TRI-Pad1)") (class "Default")
      (node (ref "XO1") (pin "1") (pinfunction "TRI_1") (pintype "input"))
    )
    (net (code "148") (name "~{CS_E}") (class "Default")
      (node (ref "IC3") (pin "14") (pinfunction "RA1_14") (pintype "bidirectional"))
      (node (ref "IC5") (pin "9") (pinfunction "~{CS}_9") (pintype "input"))
    )
    (net (code "149") (name "~{CS_L}") (class "Default")
      (node (ref "IC3") (pin "24") (pinfunction "RC11_24") (pintype "bidirectional"))
      (node (ref "U1") (pin "P$16") (pinfunction "~{CS}_P$16") (pintype "input"))
    )
    (net (code "150") (name "~{INT_E}") (class "Default")
      (node (ref "IC3") (pin "13") (pinfunction "RA0_13") (pintype "bidirectional"))
      (node (ref "IC5") (pin "4") (pinfunction "~{INT}_4") (pintype "output"))
    )
    (net (code "151") (name "~{MCLRI}") (class "Default")
      (node (ref "E1") (pin "5") (pinfunction "O4_5") (pintype "bidirectional"))
      (node (ref "J18") (pin "10") (pinfunction "B_10") (pintype "passive"))
      (node (ref "J8") (pin "1") (pinfunction "1_1") (pintype "passive"))
      (node (ref "R44") (pin "1") (pinfunction "1_1") (pintype "passive"))
    )
    (net (code "152") (name "~{MCLR}") (class "Default")
      (node (ref "E1") (pin "4") (pinfunction "I4_4") (pintype "bidirectional"))
      (node (ref "IC3") (pin "7") (pinfunction "~{MCLR}_7") (pintype "input"))
    )
  )
)
